# Supercell_1_3.net
KiCad netlist of a schematic drawn in EAGLE
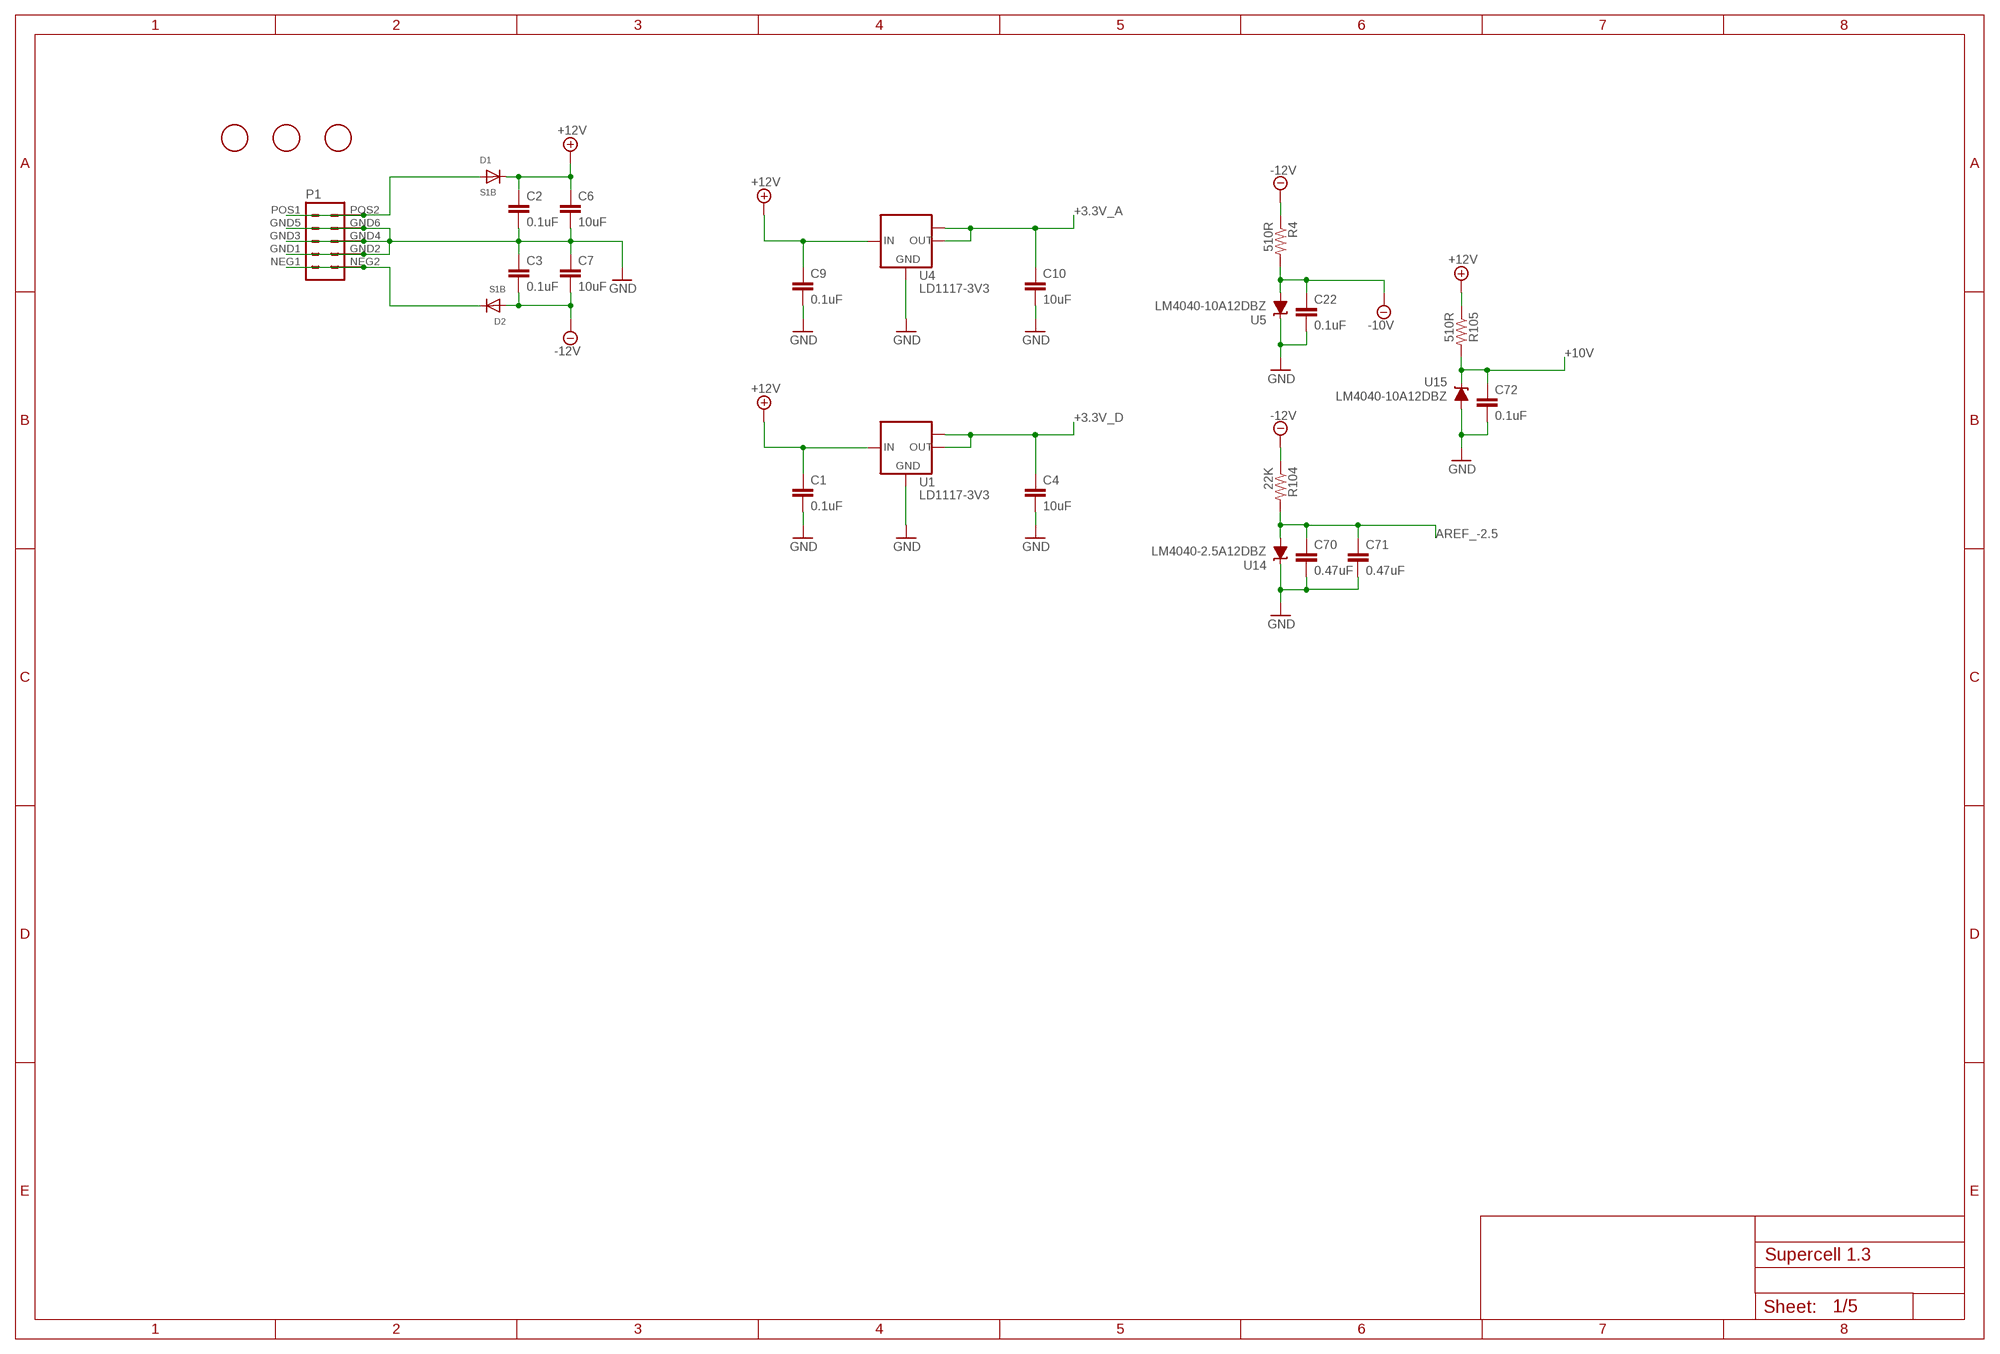
[diagram p0: schematic, sheet 1]
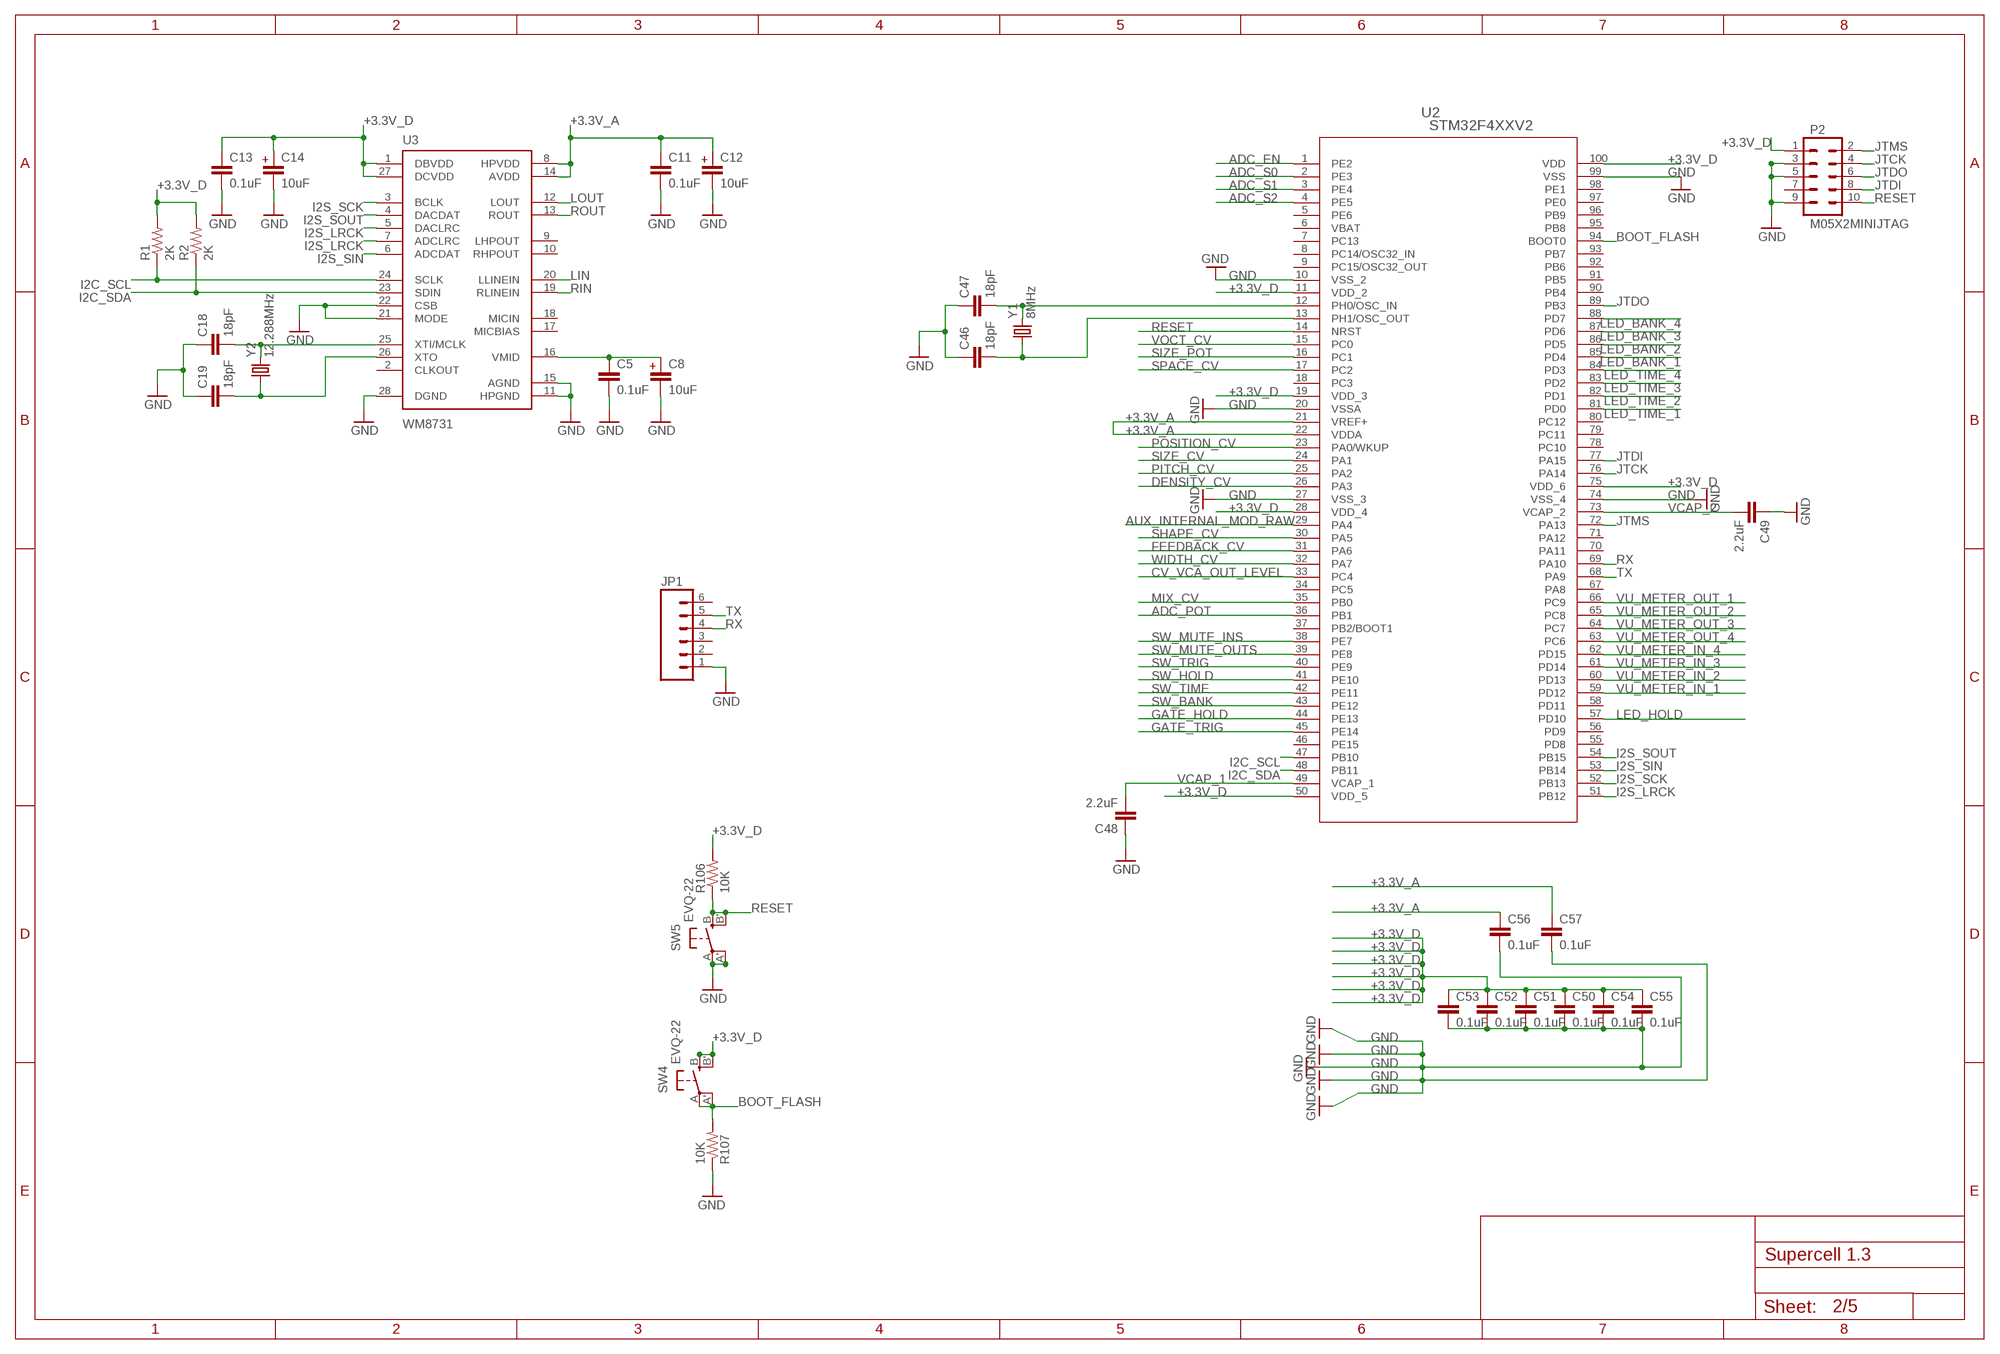
[diagram p1: schematic, sheet 2]
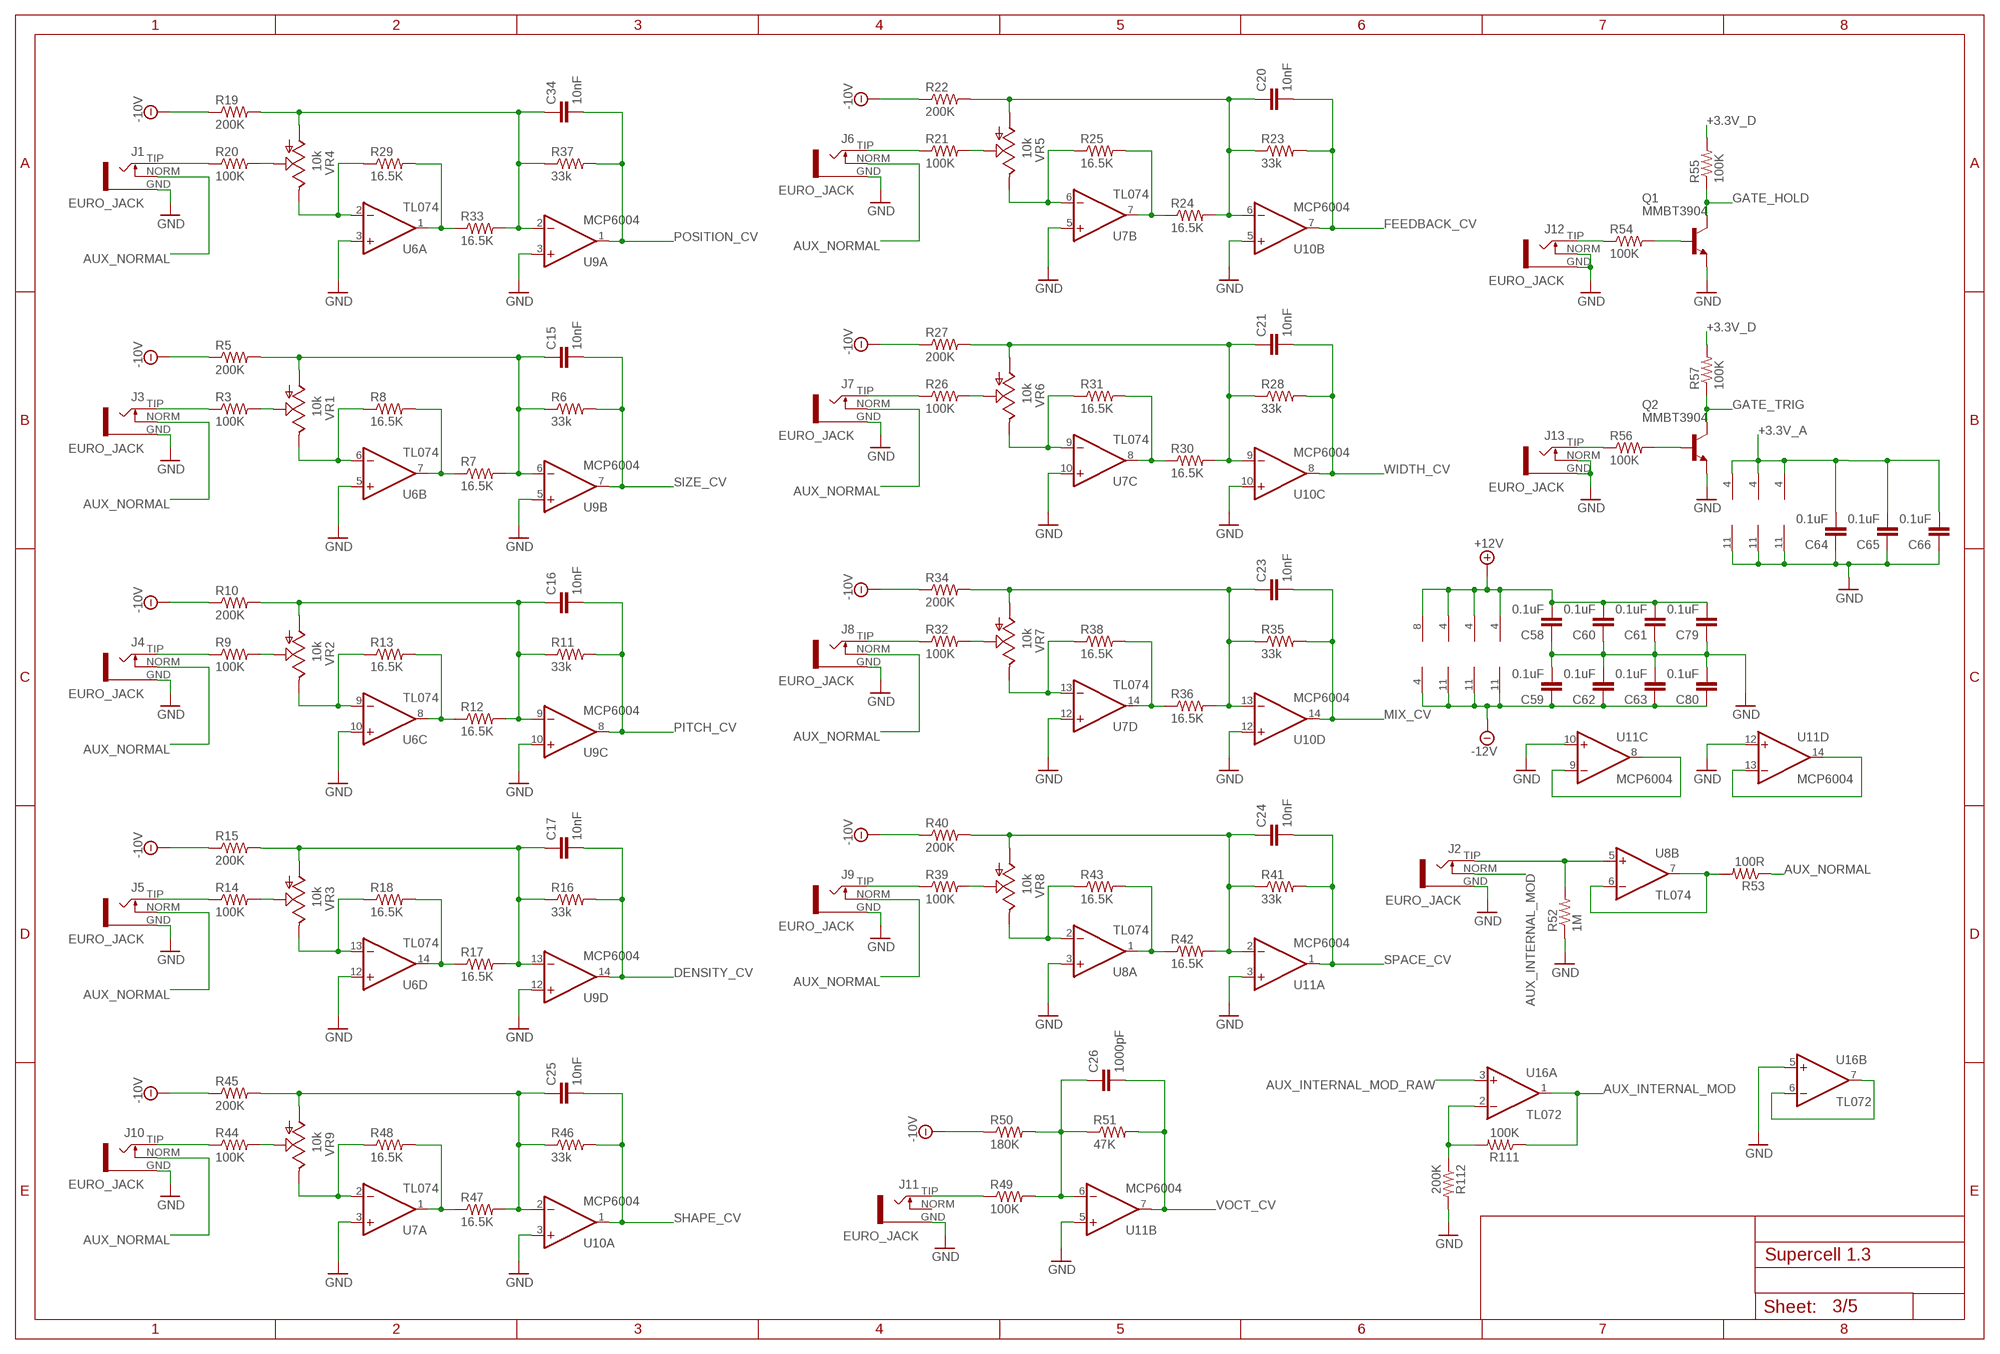
[diagram p2: schematic, sheet 3]
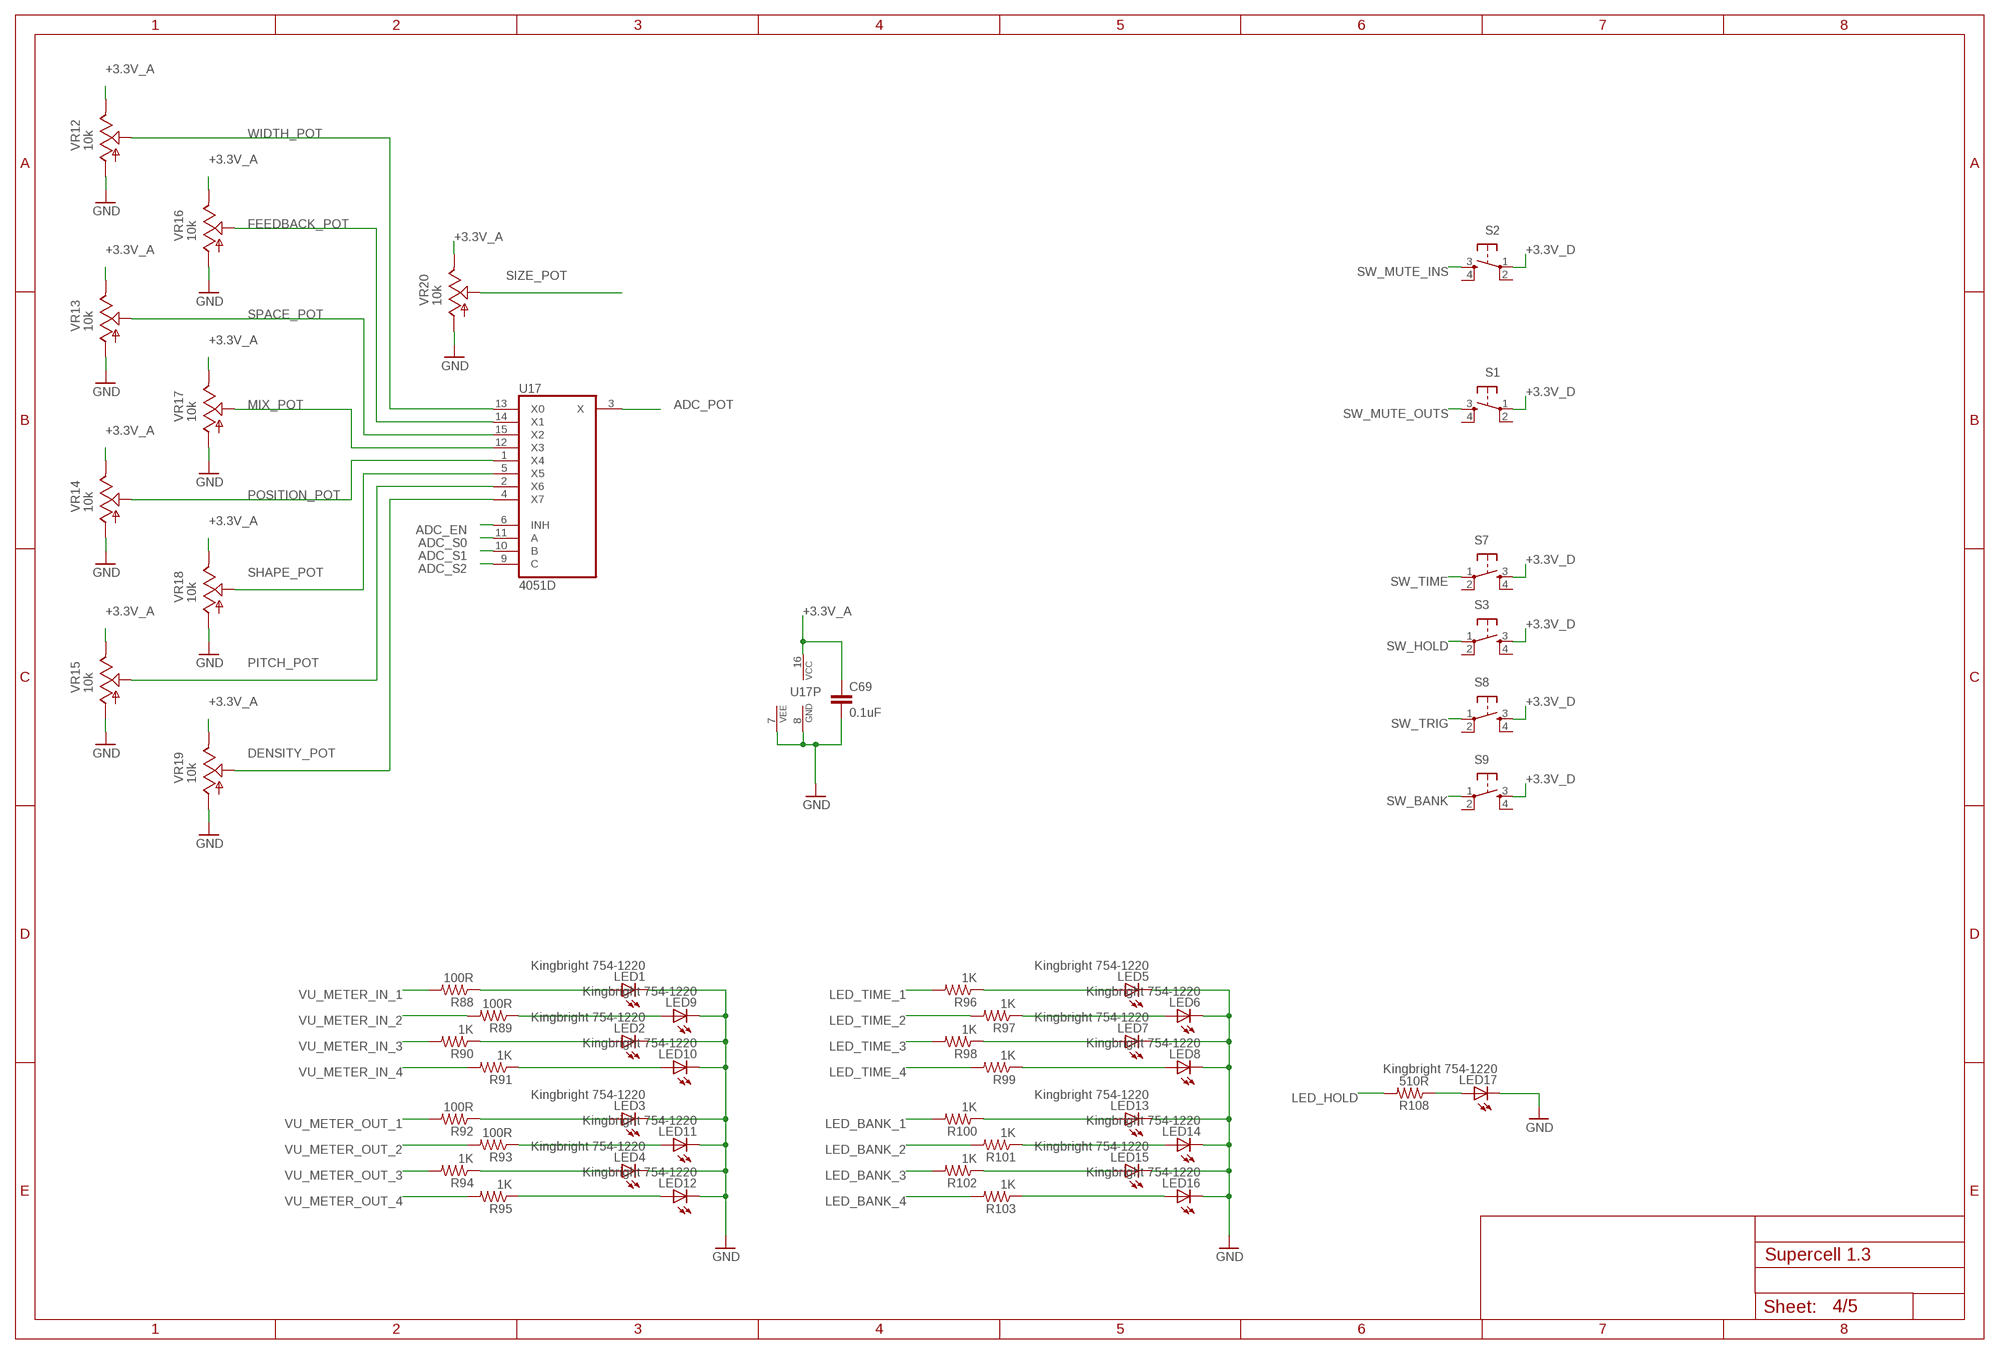
[diagram p3: schematic, sheet 4]
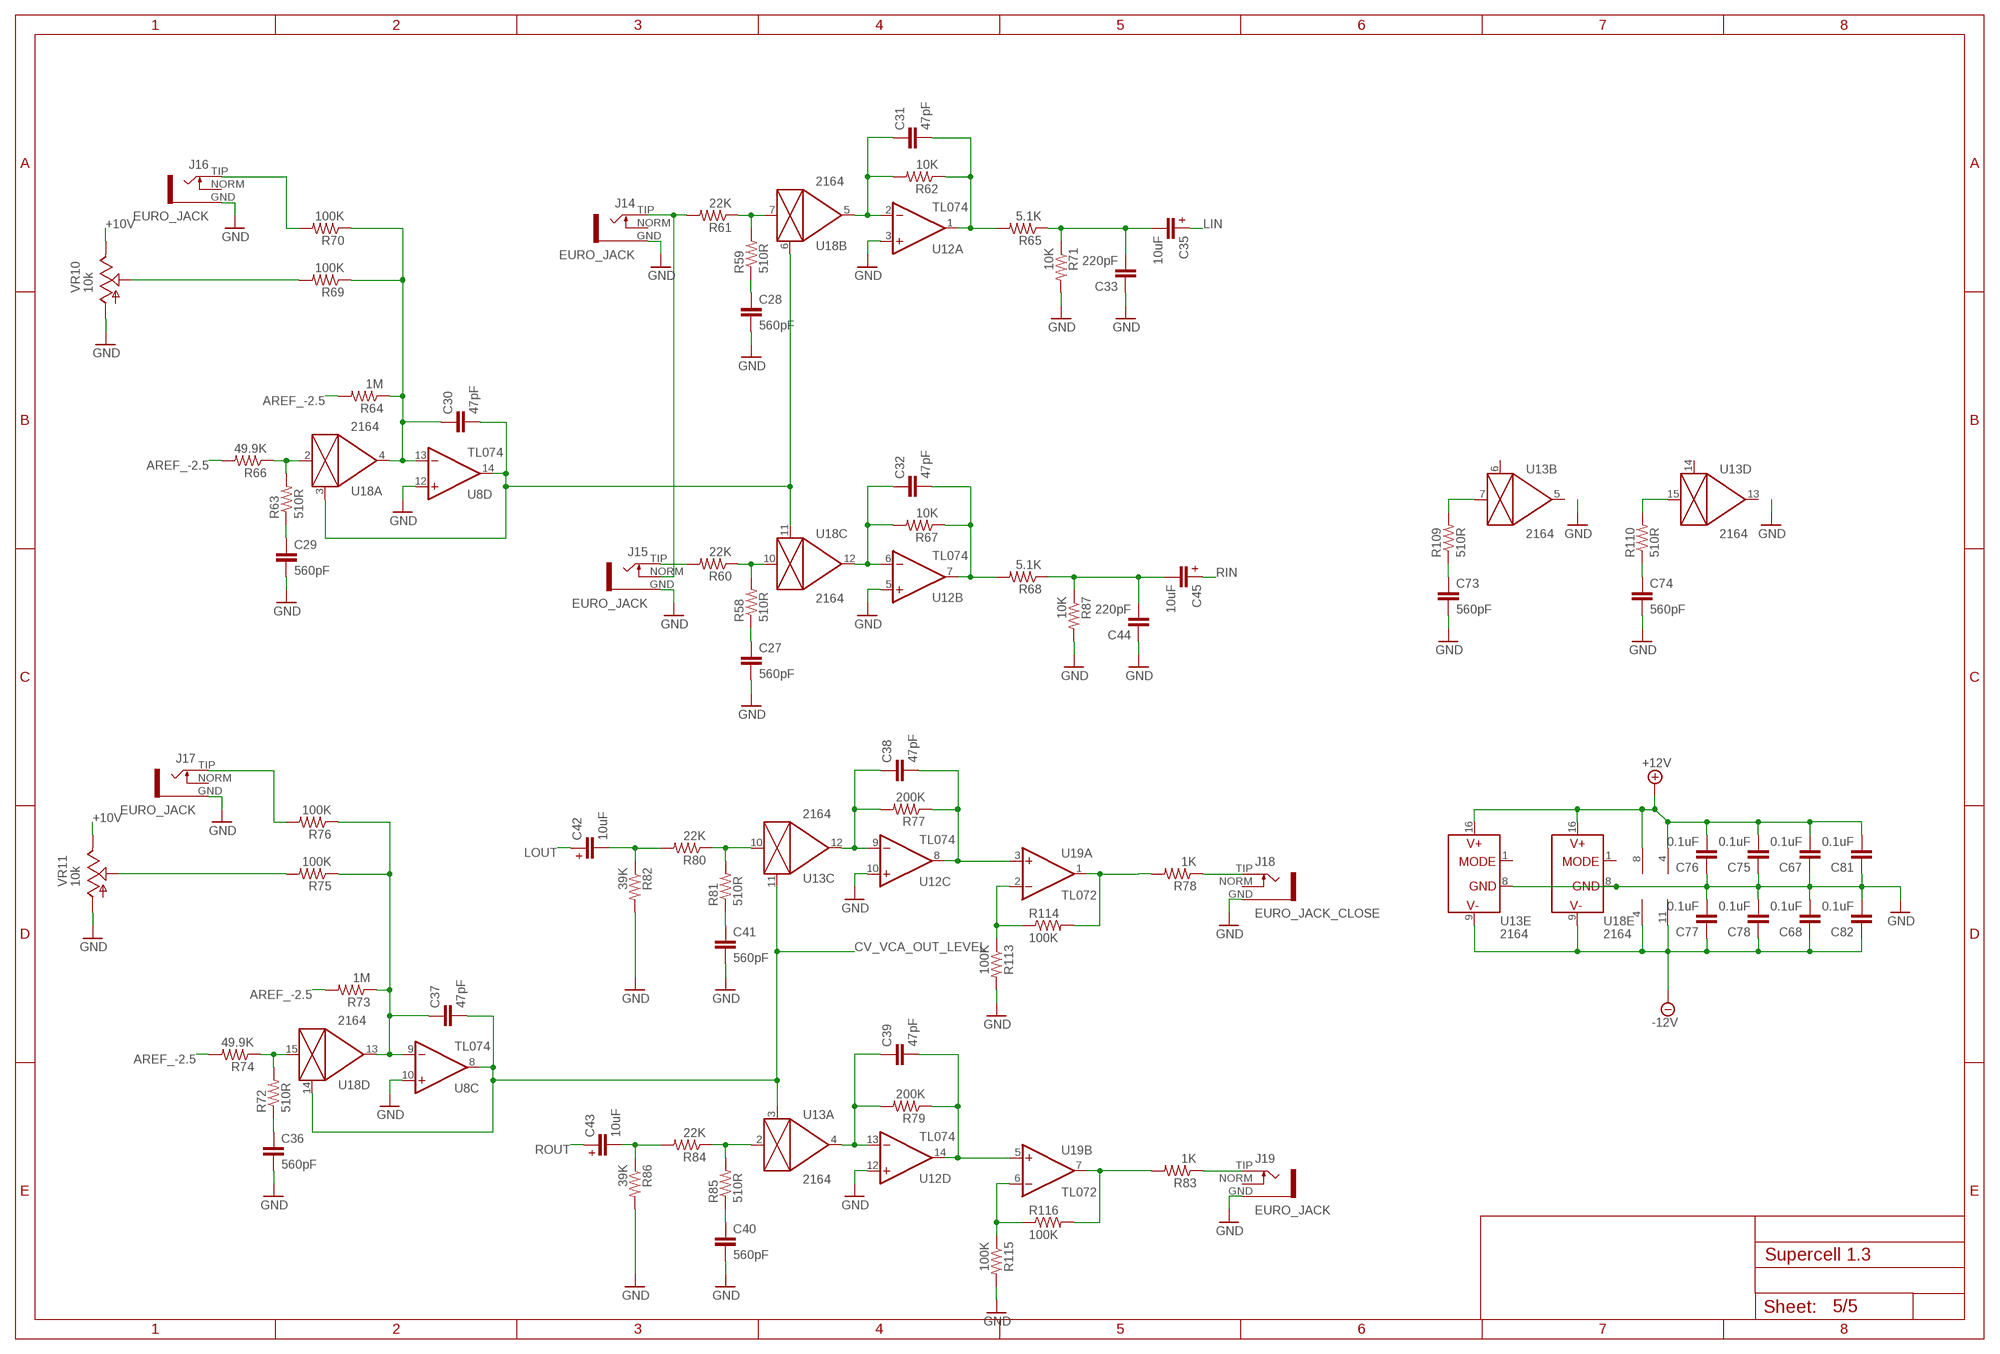
[diagram p4: schematic, sheet 5]

(export (version "E")
  (design (tool "Eeschema 10.0.6"))
  (components
    (comp (ref "C27")
      (value "560pF")
      (footprint "eagle-import:C0603")
      (libsource (lib "eagle-import") (part "rcl_C-EUC0603"))
    )
    (comp (ref "C28")
      (value "560pF")
      (footprint "eagle-import:C0603")
      (libsource (lib "eagle-import") (part "rcl_C-EUC0603"))
    )
    (comp (ref "C29")
      (value "560pF")
      (footprint "eagle-import:C0603")
      (libsource (lib "eagle-import") (part "rcl_C-EUC0603"))
    )
    (comp (ref "C30")
      (value "47pF")
      (footprint "eagle-import:C0603")
      (libsource (lib "eagle-import") (part "rcl_C-EUC0603"))
    )
    (comp (ref "C31")
      (value "47pF")
      (footprint "eagle-import:C0603")
      (libsource (lib "eagle-import") (part "rcl_C-EUC0603"))
    )
    (comp (ref "C32")
      (value "47pF")
      (footprint "eagle-import:C0603")
      (libsource (lib "eagle-import") (part "rcl_C-EUC0603"))
    )
    (comp (ref "C33")
      (value "220pF")
      (footprint "eagle-import:C0603")
      (libsource (lib "eagle-import") (part "rcl_C-EUC0603"))
    )
    (comp (ref "C35")
      (value "10uF")
      (footprint "eagle-import:EC-4X7")
      (libsource (lib "eagle-import") (part "C-EU-POL_4D"))
    )
    (comp (ref "C36")
      (value "560pF")
      (footprint "eagle-import:C0603")
      (libsource (lib "eagle-import") (part "rcl_C-EUC0603"))
    )
    (comp (ref "C37")
      (value "47pF")
      (footprint "eagle-import:C0603")
      (libsource (lib "eagle-import") (part "rcl_C-EUC0603"))
    )
    (comp (ref "C38")
      (value "47pF")
      (footprint "eagle-import:C0603")
      (libsource (lib "eagle-import") (part "rcl_C-EUC0603"))
    )
    (comp (ref "C39")
      (value "47pF")
      (footprint "eagle-import:C0603")
      (libsource (lib "eagle-import") (part "rcl_C-EUC0603"))
    )
    (comp (ref "C40")
      (value "560pF")
      (footprint "eagle-import:C0603")
      (libsource (lib "eagle-import") (part "rcl_C-EUC0603"))
    )
    (comp (ref "C41")
      (value "560pF")
      (footprint "eagle-import:C0603")
      (libsource (lib "eagle-import") (part "rcl_C-EUC0603"))
    )
    (comp (ref "C42")
      (value "10uF")
      (footprint "eagle-import:EC-4X7")
      (libsource (lib "eagle-import") (part "C-EU-POL_4D"))
    )
    (comp (ref "C43")
      (value "10uF")
      (footprint "eagle-import:EC-4X7")
      (libsource (lib "eagle-import") (part "C-EU-POL_4D"))
    )
    (comp (ref "C44")
      (value "220pF")
      (footprint "eagle-import:C0603")
      (libsource (lib "eagle-import") (part "rcl_C-EUC0603"))
    )
    (comp (ref "C45")
      (value "10uF")
      (footprint "eagle-import:EC-4X7")
      (libsource (lib "eagle-import") (part "C-EU-POL_4D"))
    )
    (comp (ref "C67")
      (value "0.1uF")
      (footprint "eagle-import:C0603")
      (libsource (lib "eagle-import") (part "rcl_C-EUC0603"))
    )
    (comp (ref "C68")
      (value "0.1uF")
      (footprint "eagle-import:C0603")
      (libsource (lib "eagle-import") (part "rcl_C-EUC0603"))
    )
    (comp (ref "C73")
      (value "560pF")
      (footprint "eagle-import:C0603")
      (libsource (lib "eagle-import") (part "rcl_C-EUC0603"))
    )
    (comp (ref "C74")
      (value "560pF")
      (footprint "eagle-import:C0603")
      (libsource (lib "eagle-import") (part "rcl_C-EUC0603"))
    )
    (comp (ref "C75")
      (value "0.1uF")
      (footprint "eagle-import:C0603")
      (libsource (lib "eagle-import") (part "rcl_C-EUC0603"))
    )
    (comp (ref "C76")
      (value "0.1uF")
      (footprint "eagle-import:C0603")
      (libsource (lib "eagle-import") (part "rcl_C-EUC0603"))
    )
    (comp (ref "C77")
      (value "0.1uF")
      (footprint "eagle-import:C0603")
      (libsource (lib "eagle-import") (part "rcl_C-EUC0603"))
    )
    (comp (ref "C78")
      (value "0.1uF")
      (footprint "eagle-import:C0603")
      (libsource (lib "eagle-import") (part "rcl_C-EUC0603"))
    )
    (comp (ref "C81")
      (value "0.1uF")
      (footprint "eagle-import:C0603")
      (libsource (lib "eagle-import") (part "rcl_C-EUC0603"))
    )
    (comp (ref "C82")
      (value "0.1uF")
      (footprint "eagle-import:C0603")
      (libsource (lib "eagle-import") (part "rcl_C-EUC0603"))
    )
    (comp (ref "J14")
      (value "EURO_JACK")
      (footprint "eagle-import:S_JACK")
      (libsource (lib "eagle-import") (part "EURO_JACK"))
    )
    (comp (ref "J15")
      (value "EURO_JACK")
      (footprint "eagle-import:S_JACK")
      (libsource (lib "eagle-import") (part "EURO_JACK"))
    )
    (comp (ref "J16")
      (value "EURO_JACK")
      (footprint "eagle-import:S_JACK")
      (libsource (lib "eagle-import") (part "EURO_JACK"))
    )
    (comp (ref "J17")
      (value "EURO_JACK")
      (footprint "eagle-import:S_JACK")
      (libsource (lib "eagle-import") (part "EURO_JACK"))
    )
    (comp (ref "J18")
      (value "EURO_JACK_CLOSE")
      (footprint "eagle-import:S_JACK_CLOSE")
      (libsource (lib "eagle-import") (part "EURO_JACK_CLOSE"))
    )
    (comp (ref "J19")
      (value "EURO_JACK")
      (footprint "eagle-import:S_JACK")
      (libsource (lib "eagle-import") (part "Electrosmith-Interface_EURO_JACK"))
    )
    (comp (ref "R58")
      (value "510R")
      (footprint "eagle-import:R0603")
      (libsource (lib "eagle-import") (part "rcl_R-US_R0603"))
    )
    (comp (ref "R59")
      (value "510R")
      (footprint "eagle-import:R0603")
      (libsource (lib "eagle-import") (part "rcl_R-US_R0603"))
    )
    (comp (ref "R60")
      (value "22K")
      (footprint "eagle-import:R0603")
      (libsource (lib "eagle-import") (part "rcl_R-US_R0603"))
    )
    (comp (ref "R61")
      (value "22K")
      (footprint "eagle-import:R0603")
      (libsource (lib "eagle-import") (part "rcl_R-US_R0603"))
    )
    (comp (ref "R62")
      (value "10K")
      (footprint "eagle-import:R0603")
      (libsource (lib "eagle-import") (part "rcl_R-US_R0603"))
    )
    (comp (ref "R63")
      (value "510R")
      (footprint "eagle-import:R0603")
      (libsource (lib "eagle-import") (part "rcl_R-US_R0603"))
    )
    (comp (ref "R64")
      (value "1M")
      (footprint "eagle-import:R0603")
      (libsource (lib "eagle-import") (part "rcl_R-US_R0603"))
    )
    (comp (ref "R65")
      (value "5.1K")
      (footprint "eagle-import:R0603")
      (libsource (lib "eagle-import") (part "rcl_R-US_R0603"))
    )
    (comp (ref "R66")
      (value "49.9K")
      (footprint "eagle-import:R0603")
      (libsource (lib "eagle-import") (part "rcl_R-US_R0603"))
    )
    (comp (ref "R67")
      (value "10K")
      (footprint "eagle-import:R0603")
      (libsource (lib "eagle-import") (part "rcl_R-US_R0603"))
    )
    (comp (ref "R68")
      (value "5.1K")
      (footprint "eagle-import:R0603")
      (libsource (lib "eagle-import") (part "rcl_R-US_R0603"))
    )
    (comp (ref "R69")
      (value "100K")
      (footprint "eagle-import:R0603")
      (libsource (lib "eagle-import") (part "rcl_R-US_R0603"))
    )
    (comp (ref "R70")
      (value "100K")
      (footprint "eagle-import:R0603")
      (libsource (lib "eagle-import") (part "rcl_R-US_R0603"))
    )
    (comp (ref "R71")
      (value "10K")
      (footprint "eagle-import:R0603")
      (libsource (lib "eagle-import") (part "rcl_R-US_R0603"))
    )
    (comp (ref "R72")
      (value "510R")
      (footprint "eagle-import:R0603")
      (libsource (lib "eagle-import") (part "rcl_R-US_R0603"))
    )
    (comp (ref "R73")
      (value "1M")
      (footprint "eagle-import:R0603")
      (libsource (lib "eagle-import") (part "rcl_R-US_R0603"))
    )
    (comp (ref "R74")
      (value "49.9K")
      (footprint "eagle-import:R0603")
      (libsource (lib "eagle-import") (part "rcl_R-US_R0603"))
    )
    (comp (ref "R75")
      (value "100K")
      (footprint "eagle-import:R0603")
      (libsource (lib "eagle-import") (part "rcl_R-US_R0603"))
    )
    (comp (ref "R76")
      (value "100K")
      (footprint "eagle-import:R0603")
      (libsource (lib "eagle-import") (part "rcl_R-US_R0603"))
    )
    (comp (ref "R77")
      (value "200K")
      (footprint "eagle-import:R0603")
      (libsource (lib "eagle-import") (part "rcl_R-US_R0603"))
    )
    (comp (ref "R78")
      (value "1K")
      (footprint "eagle-import:R0603")
      (libsource (lib "eagle-import") (part "rcl_R-US_R0603"))
    )
    (comp (ref "R79")
      (value "200K")
      (footprint "eagle-import:R0603")
      (libsource (lib "eagle-import") (part "rcl_R-US_R0603"))
    )
    (comp (ref "R80")
      (value "22K")
      (footprint "eagle-import:R0603")
      (libsource (lib "eagle-import") (part "rcl_R-US_R0603"))
    )
    (comp (ref "R81")
      (value "510R")
      (footprint "eagle-import:R0603")
      (libsource (lib "eagle-import") (part "rcl_R-US_R0603"))
    )
    (comp (ref "R82")
      (value "39K")
      (footprint "eagle-import:R0603")
      (libsource (lib "eagle-import") (part "rcl_R-US_R0603"))
    )
    (comp (ref "R83")
      (value "1K")
      (footprint "eagle-import:R0603")
      (libsource (lib "eagle-import") (part "rcl_R-US_R0603"))
    )
    (comp (ref "R84")
      (value "22K")
      (footprint "eagle-import:R0603")
      (libsource (lib "eagle-import") (part "rcl_R-US_R0603"))
    )
    (comp (ref "R85")
      (value "510R")
      (footprint "eagle-import:R0603")
      (libsource (lib "eagle-import") (part "rcl_R-US_R0603"))
    )
    (comp (ref "R86")
      (value "39K")
      (footprint "eagle-import:R0603")
      (libsource (lib "eagle-import") (part "rcl_R-US_R0603"))
    )
    (comp (ref "R87")
      (value "10K")
      (footprint "eagle-import:R0603")
      (libsource (lib "eagle-import") (part "rcl_R-US_R0603"))
    )
    (comp (ref "R109")
      (value "510R")
      (footprint "eagle-import:R0603")
      (libsource (lib "eagle-import") (part "rcl_R-US_R0603"))
    )
    (comp (ref "R110")
      (value "510R")
      (footprint "eagle-import:R0603")
      (libsource (lib "eagle-import") (part "rcl_R-US_R0603"))
    )
    (comp (ref "R113")
      (value "100K")
      (footprint "eagle-import:R0603")
      (libsource (lib "eagle-import") (part "rcl_R-US_R0603"))
    )
    (comp (ref "R114")
      (value "100K")
      (footprint "eagle-import:R0603")
      (libsource (lib "eagle-import") (part "rcl_R-US_R0603"))
    )
    (comp (ref "R115")
      (value "100K")
      (footprint "eagle-import:R0603")
      (libsource (lib "eagle-import") (part "rcl_R-US_R0603"))
    )
    (comp (ref "R116")
      (value "100K")
      (footprint "eagle-import:R0603")
      (libsource (lib "eagle-import") (part "rcl_R-US_R0603"))
    )
    (comp (ref "U8")
      (value "TL074")
      (footprint "eagle-import:SO14")
      (libsource (lib "eagle-import") (part "QUAD_OPAMPD"))
    )
    (comp (ref "U12")
      (value "TL074")
      (footprint "eagle-import:SO14")
      (libsource (lib "eagle-import") (part "QUAD_OPAMPD"))
    )
    (comp (ref "U13")
      (value "2164")
      (footprint "eagle-import:SO16")
      (libsource (lib "eagle-import") (part "SSM2164S"))
    )
    (comp (ref "U18")
      (value "2164")
      (footprint "eagle-import:SO16")
      (libsource (lib "eagle-import") (part "SSM2164S"))
    )
    (comp (ref "U19")
      (value "TL072")
      (footprint "eagle-import:SO08_BOXPIN")
      (libsource (lib "eagle-import") (part "DUAL_OPAMP"))
    )
    (comp (ref "VR10")
      (value "10k")
      (footprint "eagle-import:9MM_SNAP-IN_POT_NO_SILK")
      (libsource (lib "eagle-import") (part "POT_9MM_SNAP-IN_"))
    )
    (comp (ref "VR11")
      (value "10k")
      (footprint "eagle-import:9MM_SNAP-IN_POT_NO_SILK")
      (libsource (lib "eagle-import") (part "POT_9MM_SNAP-IN_"))
    )
    (comp (ref "C1")
      (value "0.1uF")
      (footprint "eagle-import:C0603")
      (libsource (lib "eagle-import") (part "rcl_C-EUC0603"))
    )
    (comp (ref "C2")
      (value "0.1uF")
      (footprint "eagle-import:C0603")
      (libsource (lib "eagle-import") (part "rcl_C-EUC0603"))
    )
    (comp (ref "C3")
      (value "0.1uF")
      (footprint "eagle-import:C0603")
      (libsource (lib "eagle-import") (part "rcl_C-EUC0603"))
    )
    (comp (ref "C4")
      (value "10uF")
      (footprint "eagle-import:C0805")
      (libsource (lib "eagle-import") (part "C-EUC0805"))
    )
    (comp (ref "C6")
      (value "10uF")
      (footprint "eagle-import:C0805")
      (libsource (lib "eagle-import") (part "C-EUC0805"))
    )
    (comp (ref "C7")
      (value "10uF")
      (footprint "eagle-import:C0805")
      (libsource (lib "eagle-import") (part "C-EUC0805"))
    )
    (comp (ref "C9")
      (value "0.1uF")
      (footprint "eagle-import:C0603")
      (libsource (lib "eagle-import") (part "rcl_C-EUC0603"))
    )
    (comp (ref "C10")
      (value "10uF")
      (footprint "eagle-import:C0805")
      (libsource (lib "eagle-import") (part "C-EUC0805"))
    )
    (comp (ref "C22")
      (value "0.1uF")
      (footprint "eagle-import:C0603")
      (libsource (lib "eagle-import") (part "C-EUC0603"))
    )
    (comp (ref "C70")
      (value "0.47uF")
      (footprint "eagle-import:C0603")
      (libsource (lib "eagle-import") (part "C-EUC0603"))
    )
    (comp (ref "C71")
      (value "0.47uF")
      (footprint "eagle-import:C0603")
      (libsource (lib "eagle-import") (part "C-EUC0603"))
    )
    (comp (ref "C72")
      (value "0.1uF")
      (footprint "eagle-import:C0603")
      (libsource (lib "eagle-import") (part "C-EUC0603"))
    )
    (comp (ref "D1")
      (value "S1B")
      (footprint "eagle-import:SMADIODE")
      (libsource (lib "eagle-import") (part "DIODESMA"))
    )
    (comp (ref "D2")
      (value "S1B")
      (footprint "eagle-import:SMADIODE")
      (libsource (lib "eagle-import") (part "DIODESMA"))
    )
    (comp (ref "FD1")
      (value "FIDUCIAL")
      (footprint "eagle-import:FIDUCIAL_1MM")
      (libsource (lib "eagle-import") (part "FIDUCIAL"))
    )
    (comp (ref "FD2")
      (value "FIDUCIAL")
      (footprint "eagle-import:FIDUCIAL_1MM")
      (libsource (lib "eagle-import") (part "FIDUCIAL"))
    )
    (comp (ref "FD3")
      (value "FIDUCIAL")
      (footprint "eagle-import:FIDUCIAL_1MM")
      (libsource (lib "eagle-import") (part "FIDUCIAL"))
    )
    (comp (ref "P1")
      (value "EURO_POWER_HEADERLOCK_PADS")
      (footprint "eagle-import:EURO_PWR_HEADER_LOCK")
      (libsource (lib "eagle-import") (part "EURO_POWER_HEADERLOCK_PADS"))
    )
    (comp (ref "R4")
      (value "510R")
      (footprint "eagle-import:R0603")
      (libsource (lib "eagle-import") (part "rcl_R-US_R0603"))
    )
    (comp (ref "R104")
      (value "22K")
      (footprint "eagle-import:R0603")
      (libsource (lib "eagle-import") (part "rcl_R-US_R0603"))
    )
    (comp (ref "R105")
      (value "510R")
      (footprint "eagle-import:R0603")
      (libsource (lib "eagle-import") (part "rcl_R-US_R0603"))
    )
    (comp (ref "U1")
      (value "LD1117-3V3")
      (footprint "eagle-import:SOT223")
      (libsource (lib "eagle-import") (part "LM1117MPX-3.3"))
    )
    (comp (ref "U4")
      (value "LD1117-3V3")
      (footprint "eagle-import:SOT223")
      (libsource (lib "eagle-import") (part "LM1117MPX-3.3"))
    )
    (comp (ref "U5")
      (value "LM4040-10A12DBZ")
      (footprint "eagle-import:DBZ_R-PDSO-G3")
      (fields (field (name "MPN") "LM4041A12IDBZR"))
      (libsource (lib "eagle-import") (part "LM4040-10DBZA12"))
    )
    (comp (ref "U14")
      (value "LM4040-2.5A12DBZ")
      (footprint "eagle-import:DBZ_R-PDSO-G3")
      (fields (field (name "MPN") "LM4041A12IDBZR"))
      (libsource (lib "eagle-import") (part "LM4040-2.5DBZA12"))
    )
    (comp (ref "U15")
      (value "LM4040-10A12DBZ")
      (footprint "eagle-import:DBZ_R-PDSO-G3")
      (fields (field (name "MPN") "LM4041A12IDBZR"))
      (libsource (lib "eagle-import") (part "LM4040-10DBZA12"))
    )
    (comp (ref "C5")
      (value "0.1uF")
      (footprint "eagle-import:C0603")
      (libsource (lib "eagle-import") (part "ElectroSmith_C-EUC0603"))
    )
    (comp (ref "C8")
      (value "10uF")
      (footprint "eagle-import:EC-4X7")
      (libsource (lib "eagle-import") (part "C-EU-POL_4D"))
    )
    (comp (ref "C11")
      (value "0.1uF")
      (footprint "eagle-import:C0603")
      (libsource (lib "eagle-import") (part "ElectroSmith_C-EUC0603"))
    )
    (comp (ref "C12")
      (value "10uF")
      (footprint "eagle-import:EC-4X7")
      (libsource (lib "eagle-import") (part "C-EU-POL_4D"))
    )
    (comp (ref "C13")
      (value "0.1uF")
      (footprint "eagle-import:C0603")
      (libsource (lib "eagle-import") (part "ElectroSmith_C-EUC0603"))
    )
    (comp (ref "C14")
      (value "10uF")
      (footprint "eagle-import:EC-4X7")
      (libsource (lib "eagle-import") (part "C-EU-POL_4D"))
    )
    (comp (ref "C18")
      (value "18pF")
      (footprint "eagle-import:C0603")
      (libsource (lib "eagle-import") (part "ElectroSmith_C-EUC0603"))
    )
    (comp (ref "C19")
      (value "18pF")
      (footprint "eagle-import:C0603")
      (libsource (lib "eagle-import") (part "ElectroSmith_C-EUC0603"))
    )
    (comp (ref "C46")
      (value "18pF")
      (footprint "eagle-import:C0603")
      (libsource (lib "eagle-import") (part "ElectroSmith_C-EUC0603"))
    )
    (comp (ref "C47")
      (value "18pF")
      (footprint "eagle-import:C0603")
      (libsource (lib "eagle-import") (part "ElectroSmith_C-EUC0603"))
    )
    (comp (ref "C48")
      (value "2.2uF")
      (footprint "eagle-import:C0603")
      (libsource (lib "eagle-import") (part "ElectroSmith_C-EUC0603"))
    )
    (comp (ref "C49")
      (value "2.2uF")
      (footprint "eagle-import:C0603")
      (libsource (lib "eagle-import") (part "ElectroSmith_C-EUC0603"))
    )
    (comp (ref "C50")
      (value "0.1uF")
      (footprint "eagle-import:C0603")
      (libsource (lib "eagle-import") (part "ElectroSmith_C-EUC0603"))
    )
    (comp (ref "C51")
      (value "0.1uF")
      (footprint "eagle-import:C0603")
      (libsource (lib "eagle-import") (part "ElectroSmith_C-EUC0603"))
    )
    (comp (ref "C52")
      (value "0.1uF")
      (footprint "eagle-import:C0603")
      (libsource (lib "eagle-import") (part "ElectroSmith_C-EUC0603"))
    )
    (comp (ref "C53")
      (value "0.1uF")
      (footprint "eagle-import:C0603")
      (libsource (lib "eagle-import") (part "ElectroSmith_C-EUC0603"))
    )
    (comp (ref "C54")
      (value "0.1uF")
      (footprint "eagle-import:C0603")
      (libsource (lib "eagle-import") (part "ElectroSmith_C-EUC0603"))
    )
    (comp (ref "C55")
      (value "0.1uF")
      (footprint "eagle-import:C0603")
      (libsource (lib "eagle-import") (part "ElectroSmith_C-EUC0603"))
    )
    (comp (ref "C56")
      (value "0.1uF")
      (footprint "eagle-import:C0603")
      (libsource (lib "eagle-import") (part "ElectroSmith_C-EUC0603"))
    )
    (comp (ref "C57")
      (value "0.1uF")
      (footprint "eagle-import:C0603")
      (libsource (lib "eagle-import") (part "ElectroSmith_C-EUC0603"))
    )
    (comp (ref "JP1")
      (value "M06SIP")
      (footprint "eagle-import:1X06")
      (libsource (lib "eagle-import") (part "M06SIP"))
    )
    (comp (ref "P2")
      (value "M05X2MINIJTAG")
      (footprint "eagle-import:2X5-1.27")
      (libsource (lib "eagle-import") (part "M05X2MINIJTAG"))
    )
    (comp (ref "R1")
      (value "2K")
      (footprint "eagle-import:R0603")
      (libsource (lib "eagle-import") (part "resistor_348_R-US_R0603"))
    )
    (comp (ref "R2")
      (value "2K")
      (footprint "eagle-import:R0603")
      (libsource (lib "eagle-import") (part "resistor_348_R-US_R0603"))
    )
    (comp (ref "R106")
      (value "10K")
      (footprint "eagle-import:R0603")
      (libsource (lib "eagle-import") (part "rcl_R-US_R0603"))
    )
    (comp (ref "R107")
      (value "10K")
      (footprint "eagle-import:R0603")
      (libsource (lib "eagle-import") (part "rcl_R-US_R0603"))
    )
    (comp (ref "SW4")
      (value "EVQ-22")
      (footprint "eagle-import:EVQ-Q2")
      (libsource (lib "eagle-import") (part "EVQQ2"))
    )
    (comp (ref "SW5")
      (value "EVQ-22")
      (footprint "eagle-import:EVQ-Q2")
      (libsource (lib "eagle-import") (part "EVQQ2"))
    )
    (comp (ref "U2")
      (value "STM32F4XXV2")
      (footprint "eagle-import:LQFP100-14X14MM")
      (fields (field (name "MANUFACTURER_PART_NUMBER") "stm32f4xxv2"))
      (libsource (lib "eagle-import") (part "STM32F4XXV2"))
    )
    (comp (ref "U3")
      (value "WM8731")
      (footprint "eagle-import:SSOP28")
      (libsource (lib "eagle-import") (part "WM8731"))
    )
    (comp (ref "Y1")
      (value "8MHz")
      (footprint "eagle-import:HC49UP")
      (libsource (lib "eagle-import") (part "CRYSTALHC49UP"))
    )
    (comp (ref "Y2")
      (value "12.288MHz")
      (footprint "eagle-import:HC49UP")
      (libsource (lib "eagle-import") (part "CRYSTALHC49UP"))
    )
    (comp (ref "C69")
      (value "0.1uF")
      (footprint "eagle-import:C0603")
      (libsource (lib "eagle-import") (part "ElectroSmith_C-EUC0603"))
    )
    (comp (ref "LED1")
      (value "Kingbright 754-1220")
      (footprint "eagle-import:LED_3MM_MIN")
      (libsource (lib "eagle-import") (part "LED_3MM_MIN"))
    )
    (comp (ref "LED2")
      (value "Kingbright 754-1220")
      (footprint "eagle-import:LED_3MM_MIN")
      (libsource (lib "eagle-import") (part "LED_3MM_MIN"))
    )
    (comp (ref "LED3")
      (value "Kingbright 754-1220")
      (footprint "eagle-import:LED_3MM_MIN")
      (libsource (lib "eagle-import") (part "LED_3MM_MIN"))
    )
    (comp (ref "LED4")
      (value "Kingbright 754-1220")
      (footprint "eagle-import:LED_3MM_MIN")
      (libsource (lib "eagle-import") (part "LED_3MM_MIN"))
    )
    (comp (ref "LED5")
      (value "Kingbright 754-1220")
      (footprint "eagle-import:LED_3MM_MIN")
      (libsource (lib "eagle-import") (part "LED_3MM_MIN"))
    )
    (comp (ref "LED6")
      (value "Kingbright 754-1220")
      (footprint "eagle-import:LED_3MM_MIN")
      (libsource (lib "eagle-import") (part "LED_3MM_MIN"))
    )
    (comp (ref "LED7")
      (value "Kingbright 754-1220")
      (footprint "eagle-import:LED_3MM_MIN")
      (libsource (lib "eagle-import") (part "LED_3MM_MIN"))
    )
    (comp (ref "LED8")
      (value "Kingbright 754-1220")
      (footprint "eagle-import:LED_3MM_MIN")
      (libsource (lib "eagle-import") (part "LED_3MM_MIN"))
    )
    (comp (ref "LED9")
      (value "Kingbright 754-1220")
      (footprint "eagle-import:LED_3MM_MIN")
      (libsource (lib "eagle-import") (part "LED_3MM_MIN"))
    )
    (comp (ref "LED10")
      (value "Kingbright 754-1220")
      (footprint "eagle-import:LED_3MM_MIN")
      (libsource (lib "eagle-import") (part "LED_3MM_MIN"))
    )
    (comp (ref "LED11")
      (value "Kingbright 754-1220")
      (footprint "eagle-import:LED_3MM_MIN")
      (libsource (lib "eagle-import") (part "LED_3MM_MIN"))
    )
    (comp (ref "LED12")
      (value "Kingbright 754-1220")
      (footprint "eagle-import:LED_3MM_MIN")
      (libsource (lib "eagle-import") (part "LED_3MM_MIN"))
    )
    (comp (ref "LED13")
      (value "Kingbright 754-1220")
      (footprint "eagle-import:LED_3MM_MIN")
      (libsource (lib "eagle-import") (part "LED_3MM_MIN"))
    )
    (comp (ref "LED14")
      (value "Kingbright 754-1220")
      (footprint "eagle-import:LED_3MM_MIN")
      (libsource (lib "eagle-import") (part "LED_3MM_MIN"))
    )
    (comp (ref "LED15")
      (value "Kingbright 754-1220")
      (footprint "eagle-import:LED_3MM_MIN")
      (libsource (lib "eagle-import") (part "LED_3MM_MIN"))
    )
    (comp (ref "LED16")
      (value "Kingbright 754-1220")
      (footprint "eagle-import:LED_3MM_MIN")
      (libsource (lib "eagle-import") (part "LED_3MM_MIN"))
    )
    (comp (ref "LED17")
      (value "Kingbright 754-1220")
      (footprint "eagle-import:LED_3MM_MIN")
      (libsource (lib "eagle-import") (part "LED_3MM_MIN"))
    )
    (comp (ref "R88")
      (value "100R")
      (footprint "eagle-import:R0603")
      (libsource (lib "eagle-import") (part "R-US_R0603"))
    )
    (comp (ref "R89")
      (value "100R")
      (footprint "eagle-import:R0603")
      (libsource (lib "eagle-import") (part "R-US_R0603"))
    )
    (comp (ref "R90")
      (value "1K")
      (footprint "eagle-import:R0603")
      (libsource (lib "eagle-import") (part "R-US_R0603"))
    )
    (comp (ref "R91")
      (value "1K")
      (footprint "eagle-import:R0603")
      (libsource (lib "eagle-import") (part "R-US_R0603"))
    )
    (comp (ref "R92")
      (value "100R")
      (footprint "eagle-import:R0603")
      (libsource (lib "eagle-import") (part "R-US_R0603"))
    )
    (comp (ref "R93")
      (value "100R")
      (footprint "eagle-import:R0603")
      (libsource (lib "eagle-import") (part "R-US_R0603"))
    )
    (comp (ref "R94")
      (value "1K")
      (footprint "eagle-import:R0603")
      (libsource (lib "eagle-import") (part "R-US_R0603"))
    )
    (comp (ref "R95")
      (value "1K")
      (footprint "eagle-import:R0603")
      (libsource (lib "eagle-import") (part "R-US_R0603"))
    )
    (comp (ref "R96")
      (value "1K")
      (footprint "eagle-import:R0603")
      (libsource (lib "eagle-import") (part "R-US_R0603"))
    )
    (comp (ref "R97")
      (value "1K")
      (footprint "eagle-import:R0603")
      (libsource (lib "eagle-import") (part "R-US_R0603"))
    )
    (comp (ref "R98")
      (value "1K")
      (footprint "eagle-import:R0603")
      (libsource (lib "eagle-import") (part "R-US_R0603"))
    )
    (comp (ref "R99")
      (value "1K")
      (footprint "eagle-import:R0603")
      (libsource (lib "eagle-import") (part "R-US_R0603"))
    )
    (comp (ref "R100")
      (value "1K")
      (footprint "eagle-import:R0603")
      (libsource (lib "eagle-import") (part "R-US_R0603"))
    )
    (comp (ref "R101")
      (value "1K")
      (footprint "eagle-import:R0603")
      (libsource (lib "eagle-import") (part "R-US_R0603"))
    )
    (comp (ref "R102")
      (value "1K")
      (footprint "eagle-import:R0603")
      (libsource (lib "eagle-import") (part "R-US_R0603"))
    )
    (comp (ref "R103")
      (value "1K")
      (footprint "eagle-import:R0603")
      (libsource (lib "eagle-import") (part "R-US_R0603"))
    )
    (comp (ref "R108")
      (value "510R")
      (footprint "eagle-import:R0603")
      (libsource (lib "eagle-import") (part "R-US_R0603"))
    )
    (comp (ref "S1")
      (value "TAC_SWITCHPTH")
      (footprint "eagle-import:TACTILE-PTH")
      (libsource (lib "eagle-import") (part "TAC_SWITCHPTH"))
    )
    (comp (ref "S2")
      (value "TAC_SWITCHPTH")
      (footprint "eagle-import:TACTILE-PTH")
      (libsource (lib "eagle-import") (part "TAC_SWITCHPTH"))
    )
    (comp (ref "S3")
      (value "TAC_SWITCH")
      (footprint "eagle-import:C&K_D6R")
      (libsource (lib "eagle-import") (part "TAC_SWITCH"))
    )
    (comp (ref "S7")
      (value "TAC_SWITCH")
      (footprint "eagle-import:C&K_D6R")
      (libsource (lib "eagle-import") (part "TAC_SWITCH"))
    )
    (comp (ref "S8")
      (value "TAC_SWITCH")
      (footprint "eagle-import:C&K_D6R")
      (libsource (lib "eagle-import") (part "TAC_SWITCH"))
    )
    (comp (ref "S9")
      (value "TAC_SWITCH")
      (footprint "eagle-import:C&K_D6R")
      (libsource (lib "eagle-import") (part "TAC_SWITCH"))
    )
    (comp (ref "U17")
      (value "4051D")
      (footprint "eagle-import:SO16")
      (libsource (lib "eagle-import") (part "4051D"))
    )
    (comp (ref "VR12")
      (value "10k")
      (footprint "eagle-import:9MM_SNAP-IN_POT_NO_SILK")
      (libsource (lib "eagle-import") (part "POT_9MM_SNAP-IN_"))
    )
    (comp (ref "VR13")
      (value "10k")
      (footprint "eagle-import:9MM_SNAP-IN_POT_NO_SILK")
      (libsource (lib "eagle-import") (part "POT_9MM_SNAP-IN_"))
    )
    (comp (ref "VR14")
      (value "10k")
      (footprint "eagle-import:9MM_SNAP-IN_POT_NO_SILK")
      (libsource (lib "eagle-import") (part "POT_9MM_SNAP-IN_"))
    )
    (comp (ref "VR15")
      (value "10k")
      (footprint "eagle-import:9MM_SNAP-IN_POT_NO_SILK")
      (libsource (lib "eagle-import") (part "POT_9MM_SNAP-IN_"))
    )
    (comp (ref "VR16")
      (value "10k")
      (footprint "eagle-import:9MM_SNAP-IN_POT_NO_SILK")
      (libsource (lib "eagle-import") (part "POT_9MM_SNAP-IN_"))
    )
    (comp (ref "VR17")
      (value "10k")
      (footprint "eagle-import:9MM_SNAP-IN_POT_NO_SILK")
      (libsource (lib "eagle-import") (part "POT_9MM_SNAP-IN_"))
    )
    (comp (ref "VR18")
      (value "10k")
      (footprint "eagle-import:9MM_SNAP-IN_POT_NO_SILK")
      (libsource (lib "eagle-import") (part "POT_9MM_SNAP-IN_"))
    )
    (comp (ref "VR19")
      (value "10k")
      (footprint "eagle-import:9MM_SNAP-IN_POT_NO_SILK")
      (libsource (lib "eagle-import") (part "POT_9MM_SNAP-IN_"))
    )
    (comp (ref "VR20")
      (value "10k")
      (footprint "eagle-import:9MM_SNAP-IN_POT_NO_SILK")
      (libsource (lib "eagle-import") (part "POT_9MM_SNAP-IN_"))
    )
    (comp (ref "C15")
      (value "10nF")
      (footprint "eagle-import:C0603")
      (libsource (lib "eagle-import") (part "ElectroSmith_C-EUC0603"))
    )
    (comp (ref "C16")
      (value "10nF")
      (footprint "eagle-import:C0603")
      (libsource (lib "eagle-import") (part "ElectroSmith_C-EUC0603"))
    )
    (comp (ref "C17")
      (value "10nF")
      (footprint "eagle-import:C0603")
      (libsource (lib "eagle-import") (part "ElectroSmith_C-EUC0603"))
    )
    (comp (ref "C20")
      (value "10nF")
      (footprint "eagle-import:C0603")
      (libsource (lib "eagle-import") (part "ElectroSmith_C-EUC0603"))
    )
    (comp (ref "C21")
      (value "10nF")
      (footprint "eagle-import:C0603")
      (libsource (lib "eagle-import") (part "ElectroSmith_C-EUC0603"))
    )
    (comp (ref "C23")
      (value "10nF")
      (footprint "eagle-import:C0603")
      (libsource (lib "eagle-import") (part "ElectroSmith_C-EUC0603"))
    )
    (comp (ref "C24")
      (value "10nF")
      (footprint "eagle-import:C0603")
      (libsource (lib "eagle-import") (part "ElectroSmith_C-EUC0603"))
    )
    (comp (ref "C25")
      (value "10nF")
      (footprint "eagle-import:C0603")
      (libsource (lib "eagle-import") (part "ElectroSmith_C-EUC0603"))
    )
    (comp (ref "C26")
      (value "1000pF")
      (footprint "eagle-import:C0603")
      (libsource (lib "eagle-import") (part "ElectroSmith_C-EUC0603"))
    )
    (comp (ref "C34")
      (value "10nF")
      (footprint "eagle-import:C0603")
      (libsource (lib "eagle-import") (part "ElectroSmith_C-EUC0603"))
    )
    (comp (ref "C58")
      (value "0.1uF")
      (footprint "eagle-import:C0603")
      (libsource (lib "eagle-import") (part "ElectroSmith_C-EUC0603"))
    )
    (comp (ref "C59")
      (value "0.1uF")
      (footprint "eagle-import:C0603")
      (libsource (lib "eagle-import") (part "ElectroSmith_C-EUC0603"))
    )
    (comp (ref "C60")
      (value "0.1uF")
      (footprint "eagle-import:C0603")
      (libsource (lib "eagle-import") (part "ElectroSmith_C-EUC0603"))
    )
    (comp (ref "C61")
      (value "0.1uF")
      (footprint "eagle-import:C0603")
      (libsource (lib "eagle-import") (part "ElectroSmith_C-EUC0603"))
    )
    (comp (ref "C62")
      (value "0.1uF")
      (footprint "eagle-import:C0603")
      (libsource (lib "eagle-import") (part "ElectroSmith_C-EUC0603"))
    )
    (comp (ref "C63")
      (value "0.1uF")
      (footprint "eagle-import:C0603")
      (libsource (lib "eagle-import") (part "ElectroSmith_C-EUC0603"))
    )
    (comp (ref "C64")
      (value "0.1uF")
      (footprint "eagle-import:C0603")
      (libsource (lib "eagle-import") (part "ElectroSmith_C-EUC0603"))
    )
    (comp (ref "C65")
      (value "0.1uF")
      (footprint "eagle-import:C0603")
      (libsource (lib "eagle-import") (part "ElectroSmith_C-EUC0603"))
    )
    (comp (ref "C66")
      (value "0.1uF")
      (footprint "eagle-import:C0603")
      (libsource (lib "eagle-import") (part "ElectroSmith_C-EUC0603"))
    )
    (comp (ref "C79")
      (value "0.1uF")
      (footprint "eagle-import:C0603")
      (libsource (lib "eagle-import") (part "ElectroSmith_C-EUC0603"))
    )
    (comp (ref "C80")
      (value "0.1uF")
      (footprint "eagle-import:C0603")
      (libsource (lib "eagle-import") (part "ElectroSmith_C-EUC0603"))
    )
    (comp (ref "J1")
      (value "EURO_JACK")
      (footprint "eagle-import:S_JACK")
      (libsource (lib "eagle-import") (part "EURO_JACK"))
    )
    (comp (ref "J2")
      (value "EURO_JACK")
      (footprint "eagle-import:S_JACK")
      (libsource (lib "eagle-import") (part "EURO_JACK"))
    )
    (comp (ref "J3")
      (value "EURO_JACK")
      (footprint "eagle-import:S_JACK")
      (libsource (lib "eagle-import") (part "EURO_JACK"))
    )
    (comp (ref "J4")
      (value "EURO_JACK")
      (footprint "eagle-import:S_JACK")
      (libsource (lib "eagle-import") (part "EURO_JACK"))
    )
    (comp (ref "J5")
      (value "EURO_JACK")
      (footprint "eagle-import:S_JACK")
      (libsource (lib "eagle-import") (part "EURO_JACK"))
    )
    (comp (ref "J6")
      (value "EURO_JACK")
      (footprint "eagle-import:S_JACK")
      (libsource (lib "eagle-import") (part "EURO_JACK"))
    )
    (comp (ref "J7")
      (value "EURO_JACK")
      (footprint "eagle-import:S_JACK")
      (libsource (lib "eagle-import") (part "EURO_JACK"))
    )
    (comp (ref "J8")
      (value "EURO_JACK")
      (footprint "eagle-import:S_JACK")
      (libsource (lib "eagle-import") (part "EURO_JACK"))
    )
    (comp (ref "J9")
      (value "EURO_JACK")
      (footprint "eagle-import:S_JACK")
      (libsource (lib "eagle-import") (part "EURO_JACK"))
    )
    (comp (ref "J10")
      (value "EURO_JACK")
      (footprint "eagle-import:S_JACK")
      (libsource (lib "eagle-import") (part "EURO_JACK"))
    )
    (comp (ref "J11")
      (value "EURO_JACK")
      (footprint "eagle-import:S_JACK")
      (libsource (lib "eagle-import") (part "EURO_JACK"))
    )
    (comp (ref "J12")
      (value "EURO_JACK")
      (footprint "eagle-import:S_JACK")
      (libsource (lib "eagle-import") (part "EURO_JACK"))
    )
    (comp (ref "J13")
      (value "EURO_JACK")
      (footprint "eagle-import:S_JACK")
      (libsource (lib "eagle-import") (part "EURO_JACK"))
    )
    (comp (ref "Q1")
      (value "MMBT3904")
      (footprint "eagle-import:SOT23-BEC")
      (libsource (lib "eagle-import") (part "-NPN-SOT23-BECMMBT3904LT1"))
    )
    (comp (ref "Q2")
      (value "MMBT3904")
      (footprint "eagle-import:SOT23-BEC")
      (libsource (lib "eagle-import") (part "-NPN-SOT23-BECMMBT3904LT1"))
    )
    (comp (ref "R3")
      (value "100K")
      (footprint "eagle-import:R0603")
      (libsource (lib "eagle-import") (part "R-US_R0603"))
    )
    (comp (ref "R5")
      (value "200K")
      (footprint "eagle-import:R0603")
      (libsource (lib "eagle-import") (part "R-US_R0603"))
    )
    (comp (ref "R6")
      (value "33k")
      (footprint "eagle-import:R0603")
      (libsource (lib "eagle-import") (part "R-US_R0603"))
    )
    (comp (ref "R7")
      (value "16.5K")
      (footprint "eagle-import:R0603")
      (libsource (lib "eagle-import") (part "R-US_R0603"))
    )
    (comp (ref "R8")
      (value "16.5K")
      (footprint "eagle-import:R0603")
      (libsource (lib "eagle-import") (part "R-US_R0603"))
    )
    (comp (ref "R9")
      (value "100K")
      (footprint "eagle-import:R0603")
      (libsource (lib "eagle-import") (part "R-US_R0603"))
    )
    (comp (ref "R10")
      (value "200K")
      (footprint "eagle-import:R0603")
      (libsource (lib "eagle-import") (part "R-US_R0603"))
    )
    (comp (ref "R11")
      (value "33k")
      (footprint "eagle-import:R0603")
      (libsource (lib "eagle-import") (part "R-US_R0603"))
    )
    (comp (ref "R12")
      (value "16.5K")
      (footprint "eagle-import:R0603")
      (libsource (lib "eagle-import") (part "R-US_R0603"))
    )
    (comp (ref "R13")
      (value "16.5K")
      (footprint "eagle-import:R0603")
      (libsource (lib "eagle-import") (part "R-US_R0603"))
    )
    (comp (ref "R14")
      (value "100K")
      (footprint "eagle-import:R0603")
      (libsource (lib "eagle-import") (part "R-US_R0603"))
    )
    (comp (ref "R15")
      (value "200K")
      (footprint "eagle-import:R0603")
      (libsource (lib "eagle-import") (part "R-US_R0603"))
    )
    (comp (ref "R16")
      (value "33k")
      (footprint "eagle-import:R0603")
      (libsource (lib "eagle-import") (part "R-US_R0603"))
    )
    (comp (ref "R17")
      (value "16.5K")
      (footprint "eagle-import:R0603")
      (libsource (lib "eagle-import") (part "R-US_R0603"))
    )
    (comp (ref "R18")
      (value "16.5K")
      (footprint "eagle-import:R0603")
      (libsource (lib "eagle-import") (part "R-US_R0603"))
    )
    (comp (ref "R19")
      (value "200K")
      (footprint "eagle-import:R0603")
      (libsource (lib "eagle-import") (part "R-US_R0603"))
    )
    (comp (ref "R20")
      (value "100K")
      (footprint "eagle-import:R0603")
      (libsource (lib "eagle-import") (part "R-US_R0603"))
    )
    (comp (ref "R21")
      (value "100K")
      (footprint "eagle-import:R0603")
      (libsource (lib "eagle-import") (part "R-US_R0603"))
    )
    (comp (ref "R22")
      (value "200K")
      (footprint "eagle-import:R0603")
      (libsource (lib "eagle-import") (part "R-US_R0603"))
    )
    (comp (ref "R23")
      (value "33k")
      (footprint "eagle-import:R0603")
      (libsource (lib "eagle-import") (part "R-US_R0603"))
    )
    (comp (ref "R24")
      (value "16.5K")
      (footprint "eagle-import:R0603")
      (libsource (lib "eagle-import") (part "R-US_R0603"))
    )
    (comp (ref "R25")
      (value "16.5K")
      (footprint "eagle-import:R0603")
      (libsource (lib "eagle-import") (part "R-US_R0603"))
    )
    (comp (ref "R26")
      (value "100K")
      (footprint "eagle-import:R0603")
      (libsource (lib "eagle-import") (part "R-US_R0603"))
    )
    (comp (ref "R27")
      (value "200K")
      (footprint "eagle-import:R0603")
      (libsource (lib "eagle-import") (part "R-US_R0603"))
    )
    (comp (ref "R28")
      (value "33k")
      (footprint "eagle-import:R0603")
      (libsource (lib "eagle-import") (part "R-US_R0603"))
    )
    (comp (ref "R29")
      (value "16.5K")
      (footprint "eagle-import:R0603")
      (libsource (lib "eagle-import") (part "R-US_R0603"))
    )
    (comp (ref "R30")
      (value "16.5K")
      (footprint "eagle-import:R0603")
      (libsource (lib "eagle-import") (part "R-US_R0603"))
    )
    (comp (ref "R31")
      (value "16.5K")
      (footprint "eagle-import:R0603")
      (libsource (lib "eagle-import") (part "R-US_R0603"))
    )
    (comp (ref "R32")
      (value "100K")
      (footprint "eagle-import:R0603")
      (libsource (lib "eagle-import") (part "R-US_R0603"))
    )
    (comp (ref "R33")
      (value "16.5K")
      (footprint "eagle-import:R0603")
      (libsource (lib "eagle-import") (part "R-US_R0603"))
    )
    (comp (ref "R34")
      (value "200K")
      (footprint "eagle-import:R0603")
      (libsource (lib "eagle-import") (part "R-US_R0603"))
    )
    (comp (ref "R35")
      (value "33k")
      (footprint "eagle-import:R0603")
      (libsource (lib "eagle-import") (part "R-US_R0603"))
    )
    (comp (ref "R36")
      (value "16.5K")
      (footprint "eagle-import:R0603")
      (libsource (lib "eagle-import") (part "R-US_R0603"))
    )
    (comp (ref "R37")
      (value "33k")
      (footprint "eagle-import:R0603")
      (libsource (lib "eagle-import") (part "R-US_R0603"))
    )
    (comp (ref "R38")
      (value "16.5K")
      (footprint "eagle-import:R0603")
      (libsource (lib "eagle-import") (part "R-US_R0603"))
    )
    (comp (ref "R39")
      (value "100K")
      (footprint "eagle-import:R0603")
      (libsource (lib "eagle-import") (part "R-US_R0603"))
    )
    (comp (ref "R40")
      (value "200K")
      (footprint "eagle-import:R0603")
      (libsource (lib "eagle-import") (part "R-US_R0603"))
    )
    (comp (ref "R41")
      (value "33k")
      (footprint "eagle-import:R0603")
      (libsource (lib "eagle-import") (part "R-US_R0603"))
    )
    (comp (ref "R42")
      (value "16.5K")
      (footprint "eagle-import:R0603")
      (libsource (lib "eagle-import") (part "R-US_R0603"))
    )
    (comp (ref "R43")
      (value "16.5K")
      (footprint "eagle-import:R0603")
      (libsource (lib "eagle-import") (part "R-US_R0603"))
    )
    (comp (ref "R44")
      (value "100K")
      (footprint "eagle-import:R0603")
      (libsource (lib "eagle-import") (part "R-US_R0603"))
    )
    (comp (ref "R45")
      (value "200K")
      (footprint "eagle-import:R0603")
      (libsource (lib "eagle-import") (part "R-US_R0603"))
    )
    (comp (ref "R46")
      (value "33k")
      (footprint "eagle-import:R0603")
      (libsource (lib "eagle-import") (part "R-US_R0603"))
    )
    (comp (ref "R47")
      (value "16.5K")
      (footprint "eagle-import:R0603")
      (libsource (lib "eagle-import") (part "R-US_R0603"))
    )
    (comp (ref "R48")
      (value "16.5K")
      (footprint "eagle-import:R0603")
      (libsource (lib "eagle-import") (part "R-US_R0603"))
    )
    (comp (ref "R49")
      (value "100K")
      (footprint "eagle-import:R0603")
      (libsource (lib "eagle-import") (part "R-US_R0603"))
    )
    (comp (ref "R50")
      (value "180K")
      (footprint "eagle-import:R0603")
      (libsource (lib "eagle-import") (part "R-US_R0603"))
    )
    (comp (ref "R51")
      (value "47K")
      (footprint "eagle-import:R0603")
      (libsource (lib "eagle-import") (part "R-US_R0603"))
    )
    (comp (ref "R52")
      (value "1M")
      (footprint "eagle-import:R0603")
      (libsource (lib "eagle-import") (part "R-US_R0603"))
    )
    (comp (ref "R53")
      (value "100R")
      (footprint "eagle-import:R0603")
      (libsource (lib "eagle-import") (part "R-US_R0603"))
    )
    (comp (ref "R54")
      (value "100K")
      (footprint "eagle-import:R0603")
      (libsource (lib "eagle-import") (part "R-US_R0603"))
    )
    (comp (ref "R55")
      (value "100K")
      (footprint "eagle-import:R0603")
      (libsource (lib "eagle-import") (part "R-US_R0603"))
    )
    (comp (ref "R56")
      (value "100K")
      (footprint "eagle-import:R0603")
      (libsource (lib "eagle-import") (part "R-US_R0603"))
    )
    (comp (ref "R57")
      (value "100K")
      (footprint "eagle-import:R0603")
      (libsource (lib "eagle-import") (part "R-US_R0603"))
    )
    (comp (ref "R111")
      (value "100K")
      (footprint "eagle-import:R0603")
      (libsource (lib "eagle-import") (part "R-US_R0603"))
    )
    (comp (ref "R112")
      (value "200K")
      (footprint "eagle-import:R0603")
      (libsource (lib "eagle-import") (part "R-US_R0603"))
    )
    (comp (ref "U6")
      (value "TL074")
      (footprint "eagle-import:SO14")
      (libsource (lib "eagle-import") (part "QUAD_OPAMPD"))
    )
    (comp (ref "U7")
      (value "TL074")
      (footprint "eagle-import:SO14")
      (libsource (lib "eagle-import") (part "QUAD_OPAMPD"))
    )
    (comp (ref "U9")
      (value "MCP6004")
      (footprint "eagle-import:SO14")
      (libsource (lib "eagle-import") (part "QUAD_OPAMPD"))
    )
    (comp (ref "U10")
      (value "MCP6004")
      (footprint "eagle-import:SO14")
      (libsource (lib "eagle-import") (part "QUAD_OPAMPD"))
    )
    (comp (ref "U11")
      (value "MCP6004")
      (footprint "eagle-import:SO14")
      (libsource (lib "eagle-import") (part "QUAD_OPAMPD"))
    )
    (comp (ref "U16")
      (value "TL072")
      (footprint "eagle-import:SO08_BOXPIN")
      (libsource (lib "eagle-import") (part "DUAL_OPAMP"))
    )
    (comp (ref "VR1")
      (value "10k")
      (footprint "eagle-import:9MM_SNAP-IN_POT_NO_SILK")
      (libsource (lib "eagle-import") (part "POT_9MM_SNAP-IN_"))
    )
    (comp (ref "VR2")
      (value "10k")
      (footprint "eagle-import:9MM_SNAP-IN_POT_NO_SILK")
      (libsource (lib "eagle-import") (part "POT_9MM_SNAP-IN_"))
    )
    (comp (ref "VR3")
      (value "10k")
      (footprint "eagle-import:9MM_SNAP-IN_POT_NO_SILK")
      (libsource (lib "eagle-import") (part "POT_9MM_SNAP-IN_"))
    )
    (comp (ref "VR4")
      (value "10k")
      (footprint "eagle-import:9MM_SNAP-IN_POT_NO_SILK")
      (libsource (lib "eagle-import") (part "POT_9MM_SNAP-IN_"))
    )
    (comp (ref "VR5")
      (value "10k")
      (footprint "eagle-import:9MM_SNAP-IN_POT_NO_SILK")
      (libsource (lib "eagle-import") (part "POT_9MM_SNAP-IN_"))
    )
    (comp (ref "VR6")
      (value "10k")
      (footprint "eagle-import:9MM_SNAP-IN_POT_NO_SILK")
      (libsource (lib "eagle-import") (part "POT_9MM_SNAP-IN_"))
    )
    (comp (ref "VR7")
      (value "10k")
      (footprint "eagle-import:9MM_SNAP-IN_POT_NO_SILK")
      (libsource (lib "eagle-import") (part "POT_9MM_SNAP-IN_"))
    )
    (comp (ref "VR8")
      (value "10k")
      (footprint "eagle-import:9MM_SNAP-IN_POT_NO_SILK")
      (libsource (lib "eagle-import") (part "POT_9MM_SNAP-IN_"))
    )
    (comp (ref "VR9")
      (value "10k")
      (footprint "eagle-import:9MM_SNAP-IN_POT_NO_SILK")
      (libsource (lib "eagle-import") (part "POT_9MM_SNAP-IN_"))
    )
  )
  (nets
    (net (code "1") (name "+3.3V_A") (class "Default")
      (node (ref "C10") (pin "1") (pinfunction "1_1") (pintype "passive"))
      (node (ref "C11") (pin "1") (pinfunction "1_1") (pintype "passive"))
      (node (ref "C12") (pin "P$1") (pinfunction "POS_P$1") (pintype "passive"))
      (node (ref "C56") (pin "1") (pinfunction "1_1") (pintype "passive"))
      (node (ref "C57") (pin "1") (pinfunction "1_1") (pintype "passive"))
      (node (ref "C64") (pin "2") (pinfunction "2_2") (pintype "passive"))
      (node (ref "C65") (pin "2") (pinfunction "2_2") (pintype "passive"))
      (node (ref "C66") (pin "2") (pinfunction "2_2") (pintype "passive"))
      (node (ref "C69") (pin "1") (pinfunction "1_1") (pintype "passive"))
      (node (ref "U10") (pin "4") (pinfunction "V+_4") (pintype "power_in"))
      (node (ref "U11") (pin "4") (pinfunction "V+_4") (pintype "power_in"))
      (node (ref "U17") (pin "16") (pinfunction "VCC_16") (pintype "power_in"))
      (node (ref "U2") (pin "21") (pinfunction "VREF+_21") (pintype "power_in"))
      (node (ref "U2") (pin "22") (pinfunction "VDDA_22") (pintype "power_in"))
      (node (ref "U3") (pin "14") (pinfunction "AVDD_14") (pintype "bidirectional"))
      (node (ref "U3") (pin "8") (pinfunction "HPVDD_8") (pintype "bidirectional"))
      (node (ref "U4") (pin "2") (pinfunction "OUT_2") (pintype "passive"))
      (node (ref "U4") (pin "TAB") (pinfunction "OUT1_TAB") (pintype "passive"))
      (node (ref "U9") (pin "4") (pinfunction "V+_4") (pintype "power_in"))
      (node (ref "VR12") (pin "3") (pinfunction "3_3") (pintype "passive"))
      (node (ref "VR13") (pin "3") (pinfunction "3_3") (pintype "passive"))
      (node (ref "VR14") (pin "3") (pinfunction "3_3") (pintype "passive"))
      (node (ref "VR15") (pin "3") (pinfunction "3_3") (pintype "passive"))
      (node (ref "VR16") (pin "3") (pinfunction "3_3") (pintype "passive"))
      (node (ref "VR17") (pin "3") (pinfunction "3_3") (pintype "passive"))
      (node (ref "VR18") (pin "3") (pinfunction "3_3") (pintype "passive"))
      (node (ref "VR19") (pin "3") (pinfunction "3_3") (pintype "passive"))
      (node (ref "VR20") (pin "3") (pinfunction "3_3") (pintype "passive"))
    )
    (net (code "2") (name "+3.3V_D") (class "Default")
      (node (ref "C13") (pin "1") (pinfunction "1_1") (pintype "passive"))
      (node (ref "C14") (pin "P$1") (pinfunction "POS_P$1") (pintype "passive"))
      (node (ref "C4") (pin "1") (pinfunction "1_1") (pintype "passive"))
      (node (ref "C50") (pin "1") (pinfunction "1_1") (pintype "passive"))
      (node (ref "C51") (pin "1") (pinfunction "1_1") (pintype "passive"))
      (node (ref "C52") (pin "1") (pinfunction "1_1") (pintype "passive"))
      (node (ref "C53") (pin "1") (pinfunction "1_1") (pintype "passive"))
      (node (ref "C54") (pin "1") (pinfunction "1_1") (pintype "passive"))
      (node (ref "C55") (pin "1") (pinfunction "1_1") (pintype "passive"))
      (node (ref "P2") (pin "1") (pinfunction "1_1") (pintype "passive"))
      (node (ref "R1") (pin "2") (pinfunction "2_2") (pintype "passive"))
      (node (ref "R106") (pin "2") (pinfunction "2_2") (pintype "passive"))
      (node (ref "R2") (pin "2") (pinfunction "2_2") (pintype "passive"))
      (node (ref "R55") (pin "2") (pinfunction "2_2") (pintype "passive"))
      (node (ref "R57") (pin "2") (pinfunction "2_2") (pintype "passive"))
      (node (ref "S1") (pin "1") (pinfunction "1_1") (pintype "passive"))
      (node (ref "S2") (pin "1") (pinfunction "1_1") (pintype "passive"))
      (node (ref "S3") (pin "3") (pinfunction "3_3") (pintype "passive"))
      (node (ref "S7") (pin "3") (pinfunction "3_3") (pintype "passive"))
      (node (ref "S8") (pin "3") (pinfunction "3_3") (pintype "passive"))
      (node (ref "S9") (pin "3") (pinfunction "3_3") (pintype "passive"))
      (node (ref "SW4") (pin "B") (pinfunction "S_B") (pintype "passive"))
      (node (ref "SW4") (pin "B'") (pinfunction "S1_B'") (pintype "passive"))
      (node (ref "U1") (pin "2") (pinfunction "OUT_2") (pintype "passive"))
      (node (ref "U1") (pin "TAB") (pinfunction "OUT1_TAB") (pintype "passive"))
      (node (ref "U2") (pin "100") (pinfunction "VDD_100") (pintype "power_in"))
      (node (ref "U2") (pin "11") (pinfunction "VDD_2_11") (pintype "power_in"))
      (node (ref "U2") (pin "19") (pinfunction "VDD_3_19") (pintype "power_in"))
      (node (ref "U2") (pin "28") (pinfunction "VDD_4_28") (pintype "power_in"))
      (node (ref "U2") (pin "50") (pinfunction "VDD_5_50") (pintype "power_in"))
      (node (ref "U2") (pin "75") (pinfunction "VDD_6_75") (pintype "power_in"))
      (node (ref "U3") (pin "1") (pinfunction "DBVDD_1") (pintype "bidirectional"))
      (node (ref "U3") (pin "27") (pinfunction "DCVDD_27") (pintype "bidirectional"))
    )
    (net (code "3") (name "+10V") (class "Default")
      (node (ref "C72") (pin "1") (pinfunction "1_1") (pintype "passive"))
      (node (ref "R105") (pin "2") (pinfunction "2_2") (pintype "passive"))
      (node (ref "U15") (pin "1") (pinfunction "C_1") (pintype "passive"))
      (node (ref "VR10") (pin "3") (pinfunction "3_3") (pintype "passive"))
      (node (ref "VR11") (pin "3") (pinfunction "3_3") (pintype "passive"))
    )
    (net (code "4") (name "+12V") (class "Default")
      (node (ref "C1") (pin "1") (pinfunction "1_1") (pintype "passive"))
      (node (ref "C2") (pin "1") (pinfunction "1_1") (pintype "passive"))
      (node (ref "C58") (pin "2") (pinfunction "2_2") (pintype "passive"))
      (node (ref "C6") (pin "1") (pinfunction "1_1") (pintype "passive"))
      (node (ref "C60") (pin "2") (pinfunction "2_2") (pintype "passive"))
      (node (ref "C61") (pin "2") (pinfunction "2_2") (pintype "passive"))
      (node (ref "C67") (pin "2") (pinfunction "2_2") (pintype "passive"))
      (node (ref "C75") (pin "2") (pinfunction "2_2") (pintype "passive"))
      (node (ref "C76") (pin "2") (pinfunction "2_2") (pintype "passive"))
      (node (ref "C79") (pin "2") (pinfunction "2_2") (pintype "passive"))
      (node (ref "C81") (pin "2") (pinfunction "2_2") (pintype "passive"))
      (node (ref "C9") (pin "1") (pinfunction "1_1") (pintype "passive"))
      (node (ref "D1") (pin "C") (pinfunction "C_C") (pintype "passive"))
      (node (ref "R105") (pin "1") (pinfunction "1_1") (pintype "passive"))
      (node (ref "U1") (pin "3") (pinfunction "IN_3") (pintype "input"))
      (node (ref "U12") (pin "4") (pinfunction "V+_4") (pintype "power_in"))
      (node (ref "U13") (pin "16") (pinfunction "V+_16") (pintype "power_in"))
      (node (ref "U16") (pin "8") (pinfunction "V+_8") (pintype "power_in"))
      (node (ref "U18") (pin "16") (pinfunction "V+_16") (pintype "power_in"))
      (node (ref "U19") (pin "8") (pinfunction "V+_8") (pintype "power_in"))
      (node (ref "U4") (pin "3") (pinfunction "IN_3") (pintype "input"))
      (node (ref "U6") (pin "4") (pinfunction "V+_4") (pintype "power_in"))
      (node (ref "U7") (pin "4") (pinfunction "V+_4") (pintype "power_in"))
      (node (ref "U8") (pin "4") (pinfunction "V+_4") (pintype "power_in"))
    )
    (net (code "5") (name "-10V") (class "Default")
      (node (ref "C22") (pin "1") (pinfunction "1_1") (pintype "passive"))
      (node (ref "R10") (pin "1") (pinfunction "1_1") (pintype "passive"))
      (node (ref "R15") (pin "1") (pinfunction "1_1") (pintype "passive"))
      (node (ref "R19") (pin "1") (pinfunction "1_1") (pintype "passive"))
      (node (ref "R22") (pin "1") (pinfunction "1_1") (pintype "passive"))
      (node (ref "R27") (pin "1") (pinfunction "1_1") (pintype "passive"))
      (node (ref "R34") (pin "1") (pinfunction "1_1") (pintype "passive"))
      (node (ref "R4") (pin "2") (pinfunction "2_2") (pintype "passive"))
      (node (ref "R40") (pin "1") (pinfunction "1_1") (pintype "passive"))
      (node (ref "R45") (pin "1") (pinfunction "1_1") (pintype "passive"))
      (node (ref "R5") (pin "1") (pinfunction "1_1") (pintype "passive"))
      (node (ref "R50") (pin "1") (pinfunction "1_1") (pintype "passive"))
      (node (ref "U5") (pin "2") (pinfunction "A_2") (pintype "passive"))
    )
    (net (code "6") (name "-12V") (class "Default")
      (node (ref "C3") (pin "2") (pinfunction "2_2") (pintype "passive"))
      (node (ref "C59") (pin "1") (pinfunction "1_1") (pintype "passive"))
      (node (ref "C62") (pin "1") (pinfunction "1_1") (pintype "passive"))
      (node (ref "C63") (pin "1") (pinfunction "1_1") (pintype "passive"))
      (node (ref "C68") (pin "1") (pinfunction "1_1") (pintype "passive"))
      (node (ref "C7") (pin "2") (pinfunction "2_2") (pintype "passive"))
      (node (ref "C77") (pin "1") (pinfunction "1_1") (pintype "passive"))
      (node (ref "C78") (pin "1") (pinfunction "1_1") (pintype "passive"))
      (node (ref "C80") (pin "1") (pinfunction "1_1") (pintype "passive"))
      (node (ref "C82") (pin "1") (pinfunction "1_1") (pintype "passive"))
      (node (ref "D2") (pin "A") (pinfunction "A_A") (pintype "passive"))
      (node (ref "R104") (pin "1") (pinfunction "1_1") (pintype "passive"))
      (node (ref "R4") (pin "1") (pinfunction "1_1") (pintype "passive"))
      (node (ref "U12") (pin "11") (pinfunction "V-_11") (pintype "power_in"))
      (node (ref "U13") (pin "9") (pinfunction "V-_9") (pintype "power_in"))
      (node (ref "U16") (pin "4") (pinfunction "V-_4") (pintype "power_in"))
      (node (ref "U18") (pin "9") (pinfunction "V-_9") (pintype "power_in"))
      (node (ref "U19") (pin "4") (pinfunction "V-_4") (pintype "power_in"))
      (node (ref "U6") (pin "11") (pinfunction "V-_11") (pintype "power_in"))
      (node (ref "U7") (pin "11") (pinfunction "V-_11") (pintype "power_in"))
      (node (ref "U8") (pin "11") (pinfunction "V-_11") (pintype "power_in"))
    )
    (net (code "7") (name "ADC_EN") (class "Default")
      (node (ref "U17") (pin "6") (pinfunction "INH_6") (pintype "input"))
      (node (ref "U2") (pin "1") (pinfunction "PE2_1") (pintype "bidirectional"))
    )
    (net (code "8") (name "ADC_POT") (class "Default")
      (node (ref "U17") (pin "3") (pinfunction "X_3") (pintype "bidirectional"))
      (node (ref "U2") (pin "36") (pinfunction "PB1_36") (pintype "bidirectional"))
    )
    (net (code "9") (name "ADC_S0") (class "Default")
      (node (ref "U17") (pin "11") (pinfunction "A_11") (pintype "input"))
      (node (ref "U2") (pin "2") (pinfunction "PE3_2") (pintype "bidirectional"))
    )
    (net (code "10") (name "ADC_S1") (class "Default")
      (node (ref "U17") (pin "10") (pinfunction "B_10") (pintype "input"))
      (node (ref "U2") (pin "3") (pinfunction "PE4_3") (pintype "bidirectional"))
    )
    (net (code "11") (name "ADC_S2") (class "Default")
      (node (ref "U17") (pin "9") (pinfunction "C_9") (pintype "input"))
      (node (ref "U2") (pin "4") (pinfunction "PE5_4") (pintype "bidirectional"))
    )
    (net (code "12") (name "AREF_-2.5") (class "Default")
      (node (ref "C70") (pin "1") (pinfunction "1_1") (pintype "passive"))
      (node (ref "C71") (pin "1") (pinfunction "1_1") (pintype "passive"))
      (node (ref "R104") (pin "2") (pinfunction "2_2") (pintype "passive"))
      (node (ref "R64") (pin "2") (pinfunction "2_2") (pintype "passive"))
      (node (ref "R66") (pin "2") (pinfunction "2_2") (pintype "passive"))
      (node (ref "R73") (pin "2") (pinfunction "2_2") (pintype "passive"))
      (node (ref "R74") (pin "2") (pinfunction "2_2") (pintype "passive"))
      (node (ref "U14") (pin "2") (pinfunction "A_2") (pintype "passive"))
    )
    (net (code "13") (name "AUX_INTERNAL_MOD") (class "Default")
      (node (ref "J2") (pin "NORM") (pinfunction "NORM_NORM") (pintype "passive"))
      (node (ref "R111") (pin "1") (pinfunction "1_1") (pintype "passive"))
      (node (ref "U16") (pin "1") (pinfunction "OUT_1") (pintype "output"))
    )
    (net (code "14") (name "AUX_INTERNAL_MOD_RAW") (class "Default")
      (node (ref "U16") (pin "3") (pinfunction "+IN_3") (pintype "input"))
      (node (ref "U2") (pin "29") (pinfunction "PA4_29") (pintype "bidirectional"))
    )
    (net (code "15") (name "AUX_NORMAL") (class "Default")
      (node (ref "J1") (pin "NORM") (pinfunction "NORM_NORM") (pintype "passive"))
      (node (ref "J10") (pin "NORM") (pinfunction "NORM_NORM") (pintype "passive"))
      (node (ref "J3") (pin "NORM") (pinfunction "NORM_NORM") (pintype "passive"))
      (node (ref "J4") (pin "NORM") (pinfunction "NORM_NORM") (pintype "passive"))
      (node (ref "J5") (pin "NORM") (pinfunction "NORM_NORM") (pintype "passive"))
      (node (ref "J6") (pin "NORM") (pinfunction "NORM_NORM") (pintype "passive"))
      (node (ref "J7") (pin "NORM") (pinfunction "NORM_NORM") (pintype "passive"))
      (node (ref "J8") (pin "NORM") (pinfunction "NORM_NORM") (pintype "passive"))
      (node (ref "J9") (pin "NORM") (pinfunction "NORM_NORM") (pintype "passive"))
      (node (ref "R53") (pin "1") (pinfunction "1_1") (pintype "passive"))
    )
    (net (code "16") (name "BOOT_FLASH") (class "Default")
      (node (ref "R107") (pin "2") (pinfunction "2_2") (pintype "passive"))
      (node (ref "SW4") (pin "A") (pinfunction "P_A") (pintype "passive"))
      (node (ref "SW4") (pin "A'") (pinfunction "P1_A'") (pintype "passive"))
      (node (ref "U2") (pin "94") (pinfunction "BOOT0_94") (pintype "input"))
    )
    (net (code "17") (name "CV_VCA_OUT_LEVEL") (class "Default")
      (node (ref "C37") (pin "2") (pinfunction "2_2") (pintype "passive"))
      (node (ref "U13") (pin "11") (pinfunction "CTRL_11") (pintype "input"))
      (node (ref "U13") (pin "3") (pinfunction "CTRL_3") (pintype "input"))
      (node (ref "U18") (pin "14") (pinfunction "CTRL_14") (pintype "input"))
      (node (ref "U2") (pin "33") (pinfunction "PC4_33") (pintype "bidirectional"))
      (node (ref "U8") (pin "8") (pinfunction "OUT_8") (pintype "output"))
    )
    (net (code "18") (name "DENSITY_CV") (class "Default")
      (node (ref "C17") (pin "2") (pinfunction "2_2") (pintype "passive"))
      (node (ref "R16") (pin "2") (pinfunction "2_2") (pintype "passive"))
      (node (ref "U2") (pin "26") (pinfunction "PA3_26") (pintype "bidirectional"))
      (node (ref "U9") (pin "14") (pinfunction "OUT_14") (pintype "output"))
    )
    (net (code "19") (name "DENSITY_POT") (class "Default")
      (node (ref "U17") (pin "4") (pinfunction "X7_4") (pintype "bidirectional"))
      (node (ref "VR19") (pin "2") (pinfunction "2_2") (pintype "passive"))
    )
    (net (code "20") (name "FEEDBACK_CV") (class "Default")
      (node (ref "C20") (pin "2") (pinfunction "2_2") (pintype "passive"))
      (node (ref "R23") (pin "2") (pinfunction "2_2") (pintype "passive"))
      (node (ref "U10") (pin "7") (pinfunction "OUT_7") (pintype "output"))
      (node (ref "U2") (pin "31") (pinfunction "PA6_31") (pintype "bidirectional"))
    )
    (net (code "21") (name "FEEDBACK_POT") (class "Default")
      (node (ref "U17") (pin "14") (pinfunction "X1_14") (pintype "bidirectional"))
      (node (ref "VR16") (pin "2") (pinfunction "2_2") (pintype "passive"))
    )
    (net (code "22") (name "GATE_HOLD") (class "Default")
      (node (ref "Q1") (pin "C") (pinfunction "C_C") (pintype "passive"))
      (node (ref "R55") (pin "1") (pinfunction "1_1") (pintype "passive"))
      (node (ref "U2") (pin "44") (pinfunction "PE13_44") (pintype "bidirectional"))
    )
    (net (code "23") (name "GATE_TRIG") (class "Default")
      (node (ref "Q2") (pin "C") (pinfunction "C_C") (pintype "passive"))
      (node (ref "R57") (pin "1") (pinfunction "1_1") (pintype "passive"))
      (node (ref "U2") (pin "45") (pinfunction "PE14_45") (pintype "bidirectional"))
    )
    (net (code "24") (name "GND") (class "Default")
      (node (ref "C1") (pin "2") (pinfunction "2_2") (pintype "passive"))
      (node (ref "C10") (pin "2") (pinfunction "2_2") (pintype "passive"))
      (node (ref "C11") (pin "2") (pinfunction "2_2") (pintype "passive"))
      (node (ref "C12") (pin "P$2") (pinfunction "NEG_P$2") (pintype "passive"))
      (node (ref "C13") (pin "2") (pinfunction "2_2") (pintype "passive"))
      (node (ref "C14") (pin "P$2") (pinfunction "NEG_P$2") (pintype "passive"))
      (node (ref "C18") (pin "1") (pinfunction "1_1") (pintype "passive"))
      (node (ref "C19") (pin "1") (pinfunction "1_1") (pintype "passive"))
      (node (ref "C2") (pin "2") (pinfunction "2_2") (pintype "passive"))
      (node (ref "C22") (pin "2") (pinfunction "2_2") (pintype "passive"))
      (node (ref "C27") (pin "2") (pinfunction "2_2") (pintype "passive"))
      (node (ref "C28") (pin "2") (pinfunction "2_2") (pintype "passive"))
      (node (ref "C29") (pin "2") (pinfunction "2_2") (pintype "passive"))
      (node (ref "C3") (pin "1") (pinfunction "1_1") (pintype "passive"))
      (node (ref "C33") (pin "1") (pinfunction "1_1") (pintype "passive"))
      (node (ref "C36") (pin "2") (pinfunction "2_2") (pintype "passive"))
      (node (ref "C4") (pin "2") (pinfunction "2_2") (pintype "passive"))
      (node (ref "C40") (pin "2") (pinfunction "2_2") (pintype "passive"))
      (node (ref "C41") (pin "2") (pinfunction "2_2") (pintype "passive"))
      (node (ref "C44") (pin "1") (pinfunction "1_1") (pintype "passive"))
      (node (ref "C46") (pin "1") (pinfunction "1_1") (pintype "passive"))
      (node (ref "C47") (pin "1") (pinfunction "1_1") (pintype "passive"))
      (node (ref "C48") (pin "1") (pinfunction "1_1") (pintype "passive"))
      (node (ref "C49") (pin "1") (pinfunction "1_1") (pintype "passive"))
      (node (ref "C5") (pin "2") (pinfunction "2_2") (pintype "passive"))
      (node (ref "C50") (pin "2") (pinfunction "2_2") (pintype "passive"))
      (node (ref "C51") (pin "2") (pinfunction "2_2") (pintype "passive"))
      (node (ref "C52") (pin "2") (pinfunction "2_2") (pintype "passive"))
      (node (ref "C53") (pin "2") (pinfunction "2_2") (pintype "passive"))
      (node (ref "C54") (pin "2") (pinfunction "2_2") (pintype "passive"))
      (node (ref "C55") (pin "2") (pinfunction "2_2") (pintype "passive"))
      (node (ref "C56") (pin "2") (pinfunction "2_2") (pintype "passive"))
      (node (ref "C57") (pin "2") (pinfunction "2_2") (pintype "passive"))
      (node (ref "C58") (pin "1") (pinfunction "1_1") (pintype "passive"))
      (node (ref "C59") (pin "2") (pinfunction "2_2") (pintype "passive"))
      (node (ref "C6") (pin "2") (pinfunction "2_2") (pintype "passive"))
      (node (ref "C60") (pin "1") (pinfunction "1_1") (pintype "passive"))
      (node (ref "C61") (pin "1") (pinfunction "1_1") (pintype "passive"))
      (node (ref "C62") (pin "2") (pinfunction "2_2") (pintype "passive"))
      (node (ref "C63") (pin "2") (pinfunction "2_2") (pintype "passive"))
      (node (ref "C64") (pin "1") (pinfunction "1_1") (pintype "passive"))
      (node (ref "C65") (pin "1") (pinfunction "1_1") (pintype "passive"))
      (node (ref "C66") (pin "1") (pinfunction "1_1") (pintype "passive"))
      (node (ref "C67") (pin "1") (pinfunction "1_1") (pintype "passive"))
      (node (ref "C68") (pin "2") (pinfunction "2_2") (pintype "passive"))
      (node (ref "C69") (pin "2") (pinfunction "2_2") (pintype "passive"))
      (node (ref "C7") (pin "1") (pinfunction "1_1") (pintype "passive"))
      (node (ref "C70") (pin "2") (pinfunction "2_2") (pintype "passive"))
      (node (ref "C71") (pin "2") (pinfunction "2_2") (pintype "passive"))
      (node (ref "C72") (pin "2") (pinfunction "2_2") (pintype "passive"))
      (node (ref "C73") (pin "2") (pinfunction "2_2") (pintype "passive"))
      (node (ref "C74") (pin "2") (pinfunction "2_2") (pintype "passive"))
      (node (ref "C75") (pin "1") (pinfunction "1_1") (pintype "passive"))
      (node (ref "C76") (pin "1") (pinfunction "1_1") (pintype "passive"))
      (node (ref "C77") (pin "2") (pinfunction "2_2") (pintype "passive"))
      (node (ref "C78") (pin "2") (pinfunction "2_2") (pintype "passive"))
      (node (ref "C79") (pin "1") (pinfunction "1_1") (pintype "passive"))
      (node (ref "C8") (pin "P$2") (pinfunction "NEG_P$2") (pintype "passive"))
      (node (ref "C80") (pin "2") (pinfunction "2_2") (pintype "passive"))
      (node (ref "C81") (pin "1") (pinfunction "1_1") (pintype "passive"))
      (node (ref "C82") (pin "2") (pinfunction "2_2") (pintype "passive"))
      (node (ref "C9") (pin "2") (pinfunction "2_2") (pintype "passive"))
      (node (ref "J1") (pin "GND") (pinfunction "GND_GND") (pintype "passive"))
      (node (ref "J10") (pin "GND") (pinfunction "GND_GND") (pintype "passive"))
      (node (ref "J11") (pin "GND") (pinfunction "GND_GND") (pintype "passive"))
      (node (ref "J12") (pin "GND") (pinfunction "GND_GND") (pintype "passive"))
      (node (ref "J12") (pin "NORM") (pinfunction "NORM_NORM") (pintype "passive"))
      (node (ref "J13") (pin "GND") (pinfunction "GND_GND") (pintype "passive"))
      (node (ref "J13") (pin "NORM") (pinfunction "NORM_NORM") (pintype "passive"))
      (node (ref "J14") (pin "GND") (pinfunction "GND_GND") (pintype "passive"))
      (node (ref "J15") (pin "GND") (pinfunction "GND_GND") (pintype "passive"))
      (node (ref "J16") (pin "GND") (pinfunction "GND_GND") (pintype "passive"))
      (node (ref "J17") (pin "GND") (pinfunction "GND_GND") (pintype "passive"))
      (node (ref "J18") (pin "GND") (pinfunction "GND_GND") (pintype "passive"))
      (node (ref "J19") (pin "GND") (pinfunction "GND_GND") (pintype "passive"))
      (node (ref "J2") (pin "GND") (pinfunction "GND_GND") (pintype "passive"))
      (node (ref "J3") (pin "GND") (pinfunction "GND_GND") (pintype "passive"))
      (node (ref "J4") (pin "GND") (pinfunction "GND_GND") (pintype "passive"))
      (node (ref "J5") (pin "GND") (pinfunction "GND_GND") (pintype "passive"))
      (node (ref "J6") (pin "GND") (pinfunction "GND_GND") (pintype "passive"))
      (node (ref "J7") (pin "GND") (pinfunction "GND_GND") (pintype "passive"))
      (node (ref "J8") (pin "GND") (pinfunction "GND_GND") (pintype "passive"))
      (node (ref "J9") (pin "GND") (pinfunction "GND_GND") (pintype "passive"))
      (node (ref "JP1") (pin "1") (pinfunction "1_1") (pintype "passive"))
      (node (ref "LED1") (pin "K") (pinfunction "C_K") (pintype "passive"))
      (node (ref "LED10") (pin "K") (pinfunction "C_K") (pintype "passive"))
      (node (ref "LED11") (pin "K") (pinfunction "C_K") (pintype "passive"))
      (node (ref "LED12") (pin "K") (pinfunction "C_K") (pintype "passive"))
      (node (ref "LED13") (pin "K") (pinfunction "C_K") (pintype "passive"))
      (node (ref "LED14") (pin "K") (pinfunction "C_K") (pintype "passive"))
      (node (ref "LED15") (pin "K") (pinfunction "C_K") (pintype "passive"))
      (node (ref "LED16") (pin "K") (pinfunction "C_K") (pintype "passive"))
      (node (ref "LED17") (pin "K") (pinfunction "C_K") (pintype "passive"))
      (node (ref "LED2") (pin "K") (pinfunction "C_K") (pintype "passive"))
      (node (ref "LED3") (pin "K") (pinfunction "C_K") (pintype "passive"))
      (node (ref "LED4") (pin "K") (pinfunction "C_K") (pintype "passive"))
      (node (ref "LED5") (pin "K") (pinfunction "C_K") (pintype "passive"))
      (node (ref "LED6") (pin "K") (pinfunction "C_K") (pintype "passive"))
      (node (ref "LED7") (pin "K") (pinfunction "C_K") (pintype "passive"))
      (node (ref "LED8") (pin "K") (pinfunction "C_K") (pintype "passive"))
      (node (ref "LED9") (pin "K") (pinfunction "C_K") (pintype "passive"))
      (node (ref "P1") (pin "GND1") (pinfunction "4_GND1") (pintype "bidirectional"))
      (node (ref "P1") (pin "GND2") (pinfunction "3_GND2") (pintype "bidirectional"))
      (node (ref "P1") (pin "GND3") (pinfunction "6_GND3") (pintype "bidirectional"))
      (node (ref "P1") (pin "GND4") (pinfunction "5_GND4") (pintype "bidirectional"))
      (node (ref "P1") (pin "GND5") (pinfunction "8_GND5") (pintype "bidirectional"))
      (node (ref "P1") (pin "GND6") (pinfunction "7_GND6") (pintype "bidirectional"))
      (node (ref "P2") (pin "3") (pinfunction "3_3") (pintype "passive"))
      (node (ref "P2") (pin "5") (pinfunction "5_5") (pintype "passive"))
      (node (ref "P2") (pin "9") (pinfunction "9_9") (pintype "passive"))
      (node (ref "Q1") (pin "E") (pinfunction "E_E") (pintype "passive"))
      (node (ref "Q2") (pin "E") (pinfunction "E_E") (pintype "passive"))
      (node (ref "R107") (pin "1") (pinfunction "1_1") (pintype "passive"))
      (node (ref "R112") (pin "2") (pinfunction "2_2") (pintype "passive"))
      (node (ref "R113") (pin "2") (pinfunction "2_2") (pintype "passive"))
      (node (ref "R115") (pin "2") (pinfunction "2_2") (pintype "passive"))
      (node (ref "R52") (pin "1") (pinfunction "1_1") (pintype "passive"))
      (node (ref "R71") (pin "2") (pinfunction "2_2") (pintype "passive"))
      (node (ref "R82") (pin "2") (pinfunction "2_2") (pintype "passive"))
      (node (ref "R86") (pin "2") (pinfunction "2_2") (pintype "passive"))
      (node (ref "R87") (pin "2") (pinfunction "2_2") (pintype "passive"))
      (node (ref "SW5") (pin "A") (pinfunction "P_A") (pintype "passive"))
      (node (ref "SW5") (pin "A'") (pinfunction "P1_A'") (pintype "passive"))
      (node (ref "U1") (pin "1") (pinfunction "GND_1") (pintype "input"))
      (node (ref "U10") (pin "10") (pinfunction "+IN_10") (pintype "input"))
      (node (ref "U10") (pin "11") (pinfunction "V-_11") (pintype "power_in"))
      (node (ref "U10") (pin "12") (pinfunction "+IN_12") (pintype "input"))
      (node (ref "U10") (pin "3") (pinfunction "+IN_3") (pintype "input"))
      (node (ref "U10") (pin "5") (pinfunction "+IN_5") (pintype "input"))
      (node (ref "U11") (pin "10") (pinfunction "+IN_10") (pintype "input"))
      (node (ref "U11") (pin "11") (pinfunction "V-_11") (pintype "power_in"))
      (node (ref "U11") (pin "12") (pinfunction "+IN_12") (pintype "input"))
      (node (ref "U11") (pin "3") (pinfunction "+IN_3") (pintype "input"))
      (node (ref "U11") (pin "5") (pinfunction "+IN_5") (pintype "input"))
      (node (ref "U12") (pin "10") (pinfunction "+IN_10") (pintype "input"))
      (node (ref "U12") (pin "12") (pinfunction "+IN_12") (pintype "input"))
      (node (ref "U12") (pin "3") (pinfunction "+IN_3") (pintype "input"))
      (node (ref "U12") (pin "5") (pinfunction "+IN_5") (pintype "input"))
      (node (ref "U13") (pin "8") (pinfunction "GND_8") (pintype "power_in"))
      (node (ref "U14") (pin "1") (pinfunction "C_1") (pintype "passive"))
      (node (ref "U15") (pin "2") (pinfunction "A_2") (pintype "passive"))
      (node (ref "U16") (pin "5") (pinfunction "+IN_5") (pintype "input"))
      (node (ref "U17") (pin "7") (pinfunction "VEE_7") (pintype "power_in"))
      (node (ref "U17") (pin "8") (pinfunction "GND_8") (pintype "power_in"))
      (node (ref "U18") (pin "8") (pinfunction "GND_8") (pintype "power_in"))
      (node (ref "U2") (pin "10") (pinfunction "VSS_2_10") (pintype "power_in"))
      (node (ref "U2") (pin "20") (pinfunction "VSSA_20") (pintype "power_in"))
      (node (ref "U2") (pin "27") (pinfunction "VSS_3_27") (pintype "power_in"))
      (node (ref "U2") (pin "74") (pinfunction "VSS_4_74") (pintype "power_in"))
      (node (ref "U2") (pin "99") (pinfunction "VSS_99") (pintype "power_in"))
      (node (ref "U3") (pin "11") (pinfunction "HPGND_11") (pintype "bidirectional"))
      (node (ref "U3") (pin "15") (pinfunction "AGND_15") (pintype "bidirectional"))
      (node (ref "U3") (pin "21") (pinfunction "MODE_21") (pintype "bidirectional"))
      (node (ref "U3") (pin "22") (pinfunction "CSB_22") (pintype "bidirectional"))
      (node (ref "U3") (pin "28") (pinfunction "DGND_28") (pintype "bidirectional"))
      (node (ref "U4") (pin "1") (pinfunction "GND_1") (pintype "input"))
      (node (ref "U5") (pin "1") (pinfunction "C_1") (pintype "passive"))
      (node (ref "U6") (pin "10") (pinfunction "+IN_10") (pintype "input"))
      (node (ref "U6") (pin "12") (pinfunction "+IN_12") (pintype "input"))
      (node (ref "U6") (pin "3") (pinfunction "+IN_3") (pintype "input"))
      (node (ref "U6") (pin "5") (pinfunction "+IN_5") (pintype "input"))
      (node (ref "U7") (pin "10") (pinfunction "+IN_10") (pintype "input"))
      (node (ref "U7") (pin "12") (pinfunction "+IN_12") (pintype "input"))
      (node (ref "U7") (pin "3") (pinfunction "+IN_3") (pintype "input"))
      (node (ref "U7") (pin "5") (pinfunction "+IN_5") (pintype "input"))
      (node (ref "U8") (pin "10") (pinfunction "+IN_10") (pintype "input"))
      (node (ref "U8") (pin "12") (pinfunction "+IN_12") (pintype "input"))
      (node (ref "U8") (pin "3") (pinfunction "+IN_3") (pintype "input"))
      (node (ref "U9") (pin "10") (pinfunction "+IN_10") (pintype "input"))
      (node (ref "U9") (pin "11") (pinfunction "V-_11") (pintype "power_in"))
      (node (ref "U9") (pin "12") (pinfunction "+IN_12") (pintype "input"))
      (node (ref "U9") (pin "3") (pinfunction "+IN_3") (pintype "input"))
      (node (ref "U9") (pin "5") (pinfunction "+IN_5") (pintype "input"))
      (node (ref "VR10") (pin "1") (pinfunction "1_1") (pintype "passive"))
      (node (ref "VR11") (pin "1") (pinfunction "1_1") (pintype "passive"))
      (node (ref "VR12") (pin "1") (pinfunction "1_1") (pintype "passive"))
      (node (ref "VR13") (pin "1") (pinfunction "1_1") (pintype "passive"))
      (node (ref "VR14") (pin "1") (pinfunction "1_1") (pintype "passive"))
      (node (ref "VR15") (pin "1") (pinfunction "1_1") (pintype "passive"))
      (node (ref "VR16") (pin "1") (pinfunction "1_1") (pintype "passive"))
      (node (ref "VR17") (pin "1") (pinfunction "1_1") (pintype "passive"))
      (node (ref "VR18") (pin "1") (pinfunction "1_1") (pintype "passive"))
      (node (ref "VR19") (pin "1") (pinfunction "1_1") (pintype "passive"))
      (node (ref "VR20") (pin "1") (pinfunction "1_1") (pintype "passive"))
    )
    (net (code "25") (name "I2C_SCL") (class "Default")
      (node (ref "R1") (pin "1") (pinfunction "1_1") (pintype "passive"))
      (node (ref "U2") (pin "47") (pinfunction "PB10_47") (pintype "bidirectional"))
      (node (ref "U3") (pin "24") (pinfunction "SCLK_24") (pintype "bidirectional"))
    )
    (net (code "26") (name "I2C_SDA") (class "Default")
      (node (ref "R2") (pin "1") (pinfunction "1_1") (pintype "passive"))
      (node (ref "U2") (pin "48") (pinfunction "PB11_48") (pintype "bidirectional"))
      (node (ref "U3") (pin "23") (pinfunction "SDIN_23") (pintype "bidirectional"))
    )
    (net (code "27") (name "I2S_LRCK") (class "Default")
      (node (ref "U2") (pin "51") (pinfunction "PB12_51") (pintype "bidirectional"))
      (node (ref "U3") (pin "5") (pinfunction "DACLRC_5") (pintype "bidirectional"))
      (node (ref "U3") (pin "7") (pinfunction "ADCLRC_7") (pintype "bidirectional"))
    )
    (net (code "28") (name "I2S_SCK") (class "Default")
      (node (ref "U2") (pin "52") (pinfunction "PB13_52") (pintype "bidirectional"))
      (node (ref "U3") (pin "3") (pinfunction "BCLK_3") (pintype "bidirectional"))
    )
    (net (code "29") (name "I2S_SIN") (class "Default")
      (node (ref "U2") (pin "53") (pinfunction "PB14_53") (pintype "bidirectional"))
      (node (ref "U3") (pin "6") (pinfunction "ADCDAT_6") (pintype "bidirectional"))
    )
    (net (code "30") (name "I2S_SOUT") (class "Default")
      (node (ref "U2") (pin "54") (pinfunction "PB15_54") (pintype "bidirectional"))
      (node (ref "U3") (pin "4") (pinfunction "DACDAT_4") (pintype "bidirectional"))
    )
    (net (code "31") (name "JTCK") (class "Default")
      (node (ref "P2") (pin "4") (pinfunction "4_4") (pintype "passive"))
      (node (ref "U2") (pin "76") (pinfunction "PA14_76") (pintype "bidirectional"))
    )
    (net (code "32") (name "JTDI") (class "Default")
      (node (ref "P2") (pin "8") (pinfunction "8_8") (pintype "passive"))
      (node (ref "U2") (pin "77") (pinfunction "PA15_77") (pintype "bidirectional"))
    )
    (net (code "33") (name "JTDO") (class "Default")
      (node (ref "P2") (pin "6") (pinfunction "6_6") (pintype "passive"))
      (node (ref "U2") (pin "89") (pinfunction "PB3_89") (pintype "bidirectional"))
    )
    (net (code "34") (name "JTMS") (class "Default")
      (node (ref "P2") (pin "2") (pinfunction "2_2") (pintype "passive"))
      (node (ref "U2") (pin "72") (pinfunction "PA13_72") (pintype "bidirectional"))
    )
    (net (code "35") (name "LED_BANK_1") (class "Default")
      (node (ref "R100") (pin "2") (pinfunction "2_2") (pintype "passive"))
      (node (ref "U2") (pin "85") (pinfunction "PD4_85") (pintype "bidirectional"))
    )
    (net (code "36") (name "LED_BANK_2") (class "Default")
      (node (ref "R101") (pin "2") (pinfunction "2_2") (pintype "passive"))
      (node (ref "U2") (pin "86") (pinfunction "PD5_86") (pintype "bidirectional"))
    )
    (net (code "37") (name "LED_BANK_3") (class "Default")
      (node (ref "R102") (pin "2") (pinfunction "2_2") (pintype "passive"))
      (node (ref "U2") (pin "87") (pinfunction "PD6_87") (pintype "bidirectional"))
    )
    (net (code "38") (name "LED_BANK_4") (class "Default")
      (node (ref "R103") (pin "2") (pinfunction "2_2") (pintype "passive"))
      (node (ref "U2") (pin "88") (pinfunction "PD7_88") (pintype "bidirectional"))
    )
    (net (code "39") (name "LED_HOLD") (class "Default")
      (node (ref "R108") (pin "2") (pinfunction "2_2") (pintype "passive"))
      (node (ref "U2") (pin "57") (pinfunction "PD10_57") (pintype "bidirectional"))
    )
    (net (code "40") (name "LED_TIME_1") (class "Default")
      (node (ref "R96") (pin "2") (pinfunction "2_2") (pintype "passive"))
      (node (ref "U2") (pin "81") (pinfunction "PD0_81") (pintype "bidirectional"))
    )
    (net (code "41") (name "LED_TIME_2") (class "Default")
      (node (ref "R97") (pin "2") (pinfunction "2_2") (pintype "passive"))
      (node (ref "U2") (pin "82") (pinfunction "PD1_82") (pintype "bidirectional"))
    )
    (net (code "42") (name "LED_TIME_3") (class "Default")
      (node (ref "R98") (pin "2") (pinfunction "2_2") (pintype "passive"))
      (node (ref "U2") (pin "83") (pinfunction "PD2_83") (pintype "bidirectional"))
    )
    (net (code "43") (name "LED_TIME_4") (class "Default")
      (node (ref "R99") (pin "2") (pinfunction "2_2") (pintype "passive"))
      (node (ref "U2") (pin "84") (pinfunction "PD3_84") (pintype "bidirectional"))
    )
    (net (code "44") (name "LIN") (class "Default")
      (node (ref "C35") (pin "P$1") (pinfunction "POS_P$1") (pintype "passive"))
      (node (ref "U3") (pin "20") (pinfunction "LLINEIN_20") (pintype "bidirectional"))
    )
    (net (code "45") (name "LOUT") (class "Default")
      (node (ref "C42") (pin "P$1") (pinfunction "POS_P$1") (pintype "passive"))
      (node (ref "U3") (pin "12") (pinfunction "LOUT_12") (pintype "bidirectional"))
    )
    (net (code "46") (name "MIX_CV") (class "Default")
      (node (ref "C23") (pin "2") (pinfunction "2_2") (pintype "passive"))
      (node (ref "R35") (pin "2") (pinfunction "2_2") (pintype "passive"))
      (node (ref "U10") (pin "14") (pinfunction "OUT_14") (pintype "output"))
      (node (ref "U2") (pin "35") (pinfunction "PB0_35") (pintype "bidirectional"))
    )
    (net (code "47") (name "MIX_POT") (class "Default")
      (node (ref "U17") (pin "12") (pinfunction "X3_12") (pintype "bidirectional"))
      (node (ref "VR17") (pin "2") (pinfunction "2_2") (pintype "passive"))
    )
    (net (code "48") (name "Net-(C8-POS)") (class "Default")
      (node (ref "C5") (pin "1") (pinfunction "1_1") (pintype "passive"))
      (node (ref "C8") (pin "P$1") (pinfunction "POS_P$1") (pintype "passive"))
      (node (ref "U3") (pin "16") (pinfunction "VMID_16") (pintype "bidirectional"))
    )
    (net (code "49") (name "Net-(C27-Pad1)") (class "Default")
      (node (ref "C27") (pin "1") (pinfunction "1_1") (pintype "passive"))
      (node (ref "R58") (pin "1") (pinfunction "1_1") (pintype "passive"))
    )
    (net (code "50") (name "Net-(C28-Pad1)") (class "Default")
      (node (ref "C28") (pin "1") (pinfunction "1_1") (pintype "passive"))
      (node (ref "R59") (pin "1") (pinfunction "1_1") (pintype "passive"))
    )
    (net (code "51") (name "Net-(C29-Pad1)") (class "Default")
      (node (ref "C29") (pin "1") (pinfunction "1_1") (pintype "passive"))
      (node (ref "R63") (pin "1") (pinfunction "1_1") (pintype "passive"))
    )
    (net (code "52") (name "Net-(C35-NEG)") (class "Default")
      (node (ref "C33") (pin "2") (pinfunction "2_2") (pintype "passive"))
      (node (ref "C35") (pin "P$2") (pinfunction "NEG_P$2") (pintype "passive"))
      (node (ref "R65") (pin "1") (pinfunction "1_1") (pintype "passive"))
      (node (ref "R71") (pin "1") (pinfunction "1_1") (pintype "passive"))
    )
    (net (code "53") (name "Net-(C36-Pad1)") (class "Default")
      (node (ref "C36") (pin "1") (pinfunction "1_1") (pintype "passive"))
      (node (ref "R72") (pin "1") (pinfunction "1_1") (pintype "passive"))
    )
    (net (code "54") (name "Net-(C40-Pad1)") (class "Default")
      (node (ref "C40") (pin "1") (pinfunction "1_1") (pintype "passive"))
      (node (ref "R85") (pin "1") (pinfunction "1_1") (pintype "passive"))
    )
    (net (code "55") (name "Net-(C41-Pad1)") (class "Default")
      (node (ref "C41") (pin "1") (pinfunction "1_1") (pintype "passive"))
      (node (ref "R81") (pin "1") (pinfunction "1_1") (pintype "passive"))
    )
    (net (code "56") (name "Net-(C42-NEG)") (class "Default")
      (node (ref "C42") (pin "P$2") (pinfunction "NEG_P$2") (pintype "passive"))
      (node (ref "R80") (pin "2") (pinfunction "2_2") (pintype "passive"))
      (node (ref "R82") (pin "1") (pinfunction "1_1") (pintype "passive"))
    )
    (net (code "57") (name "Net-(C43-NEG)") (class "Default")
      (node (ref "C43") (pin "P$2") (pinfunction "NEG_P$2") (pintype "passive"))
      (node (ref "R84") (pin "2") (pinfunction "2_2") (pintype "passive"))
      (node (ref "R86") (pin "1") (pinfunction "1_1") (pintype "passive"))
    )
    (net (code "58") (name "Net-(C45-NEG)") (class "Default")
      (node (ref "C44") (pin "2") (pinfunction "2_2") (pintype "passive"))
      (node (ref "C45") (pin "P$2") (pinfunction "NEG_P$2") (pintype "passive"))
      (node (ref "R68") (pin "1") (pinfunction "1_1") (pintype "passive"))
      (node (ref "R87") (pin "1") (pinfunction "1_1") (pintype "passive"))
    )
    (net (code "59") (name "Net-(C73-Pad1)") (class "Default")
      (node (ref "C73") (pin "1") (pinfunction "1_1") (pintype "passive"))
      (node (ref "R109") (pin "1") (pinfunction "1_1") (pintype "passive"))
    )
    (net (code "60") (name "Net-(C74-Pad1)") (class "Default")
      (node (ref "C74") (pin "1") (pinfunction "1_1") (pintype "passive"))
      (node (ref "R110") (pin "1") (pinfunction "1_1") (pintype "passive"))
    )
    (net (code "61") (name "Net-(J1-PadTIP)") (class "Default")
      (node (ref "J1") (pin "TIP") (pinfunction "TIP_TIP") (pintype "passive"))
      (node (ref "R20") (pin "1") (pinfunction "1_1") (pintype "passive"))
    )
    (net (code "62") (name "Net-(J3-PadTIP)") (class "Default")
      (node (ref "J3") (pin "TIP") (pinfunction "TIP_TIP") (pintype "passive"))
      (node (ref "R3") (pin "1") (pinfunction "1_1") (pintype "passive"))
    )
    (net (code "63") (name "Net-(J4-PadTIP)") (class "Default")
      (node (ref "J4") (pin "TIP") (pinfunction "TIP_TIP") (pintype "passive"))
      (node (ref "R9") (pin "1") (pinfunction "1_1") (pintype "passive"))
    )
    (net (code "64") (name "Net-(J5-PadTIP)") (class "Default")
      (node (ref "J5") (pin "TIP") (pinfunction "TIP_TIP") (pintype "passive"))
      (node (ref "R14") (pin "1") (pinfunction "1_1") (pintype "passive"))
    )
    (net (code "65") (name "Net-(J6-PadTIP)") (class "Default")
      (node (ref "J6") (pin "TIP") (pinfunction "TIP_TIP") (pintype "passive"))
      (node (ref "R21") (pin "1") (pinfunction "1_1") (pintype "passive"))
    )
    (net (code "66") (name "Net-(J7-PadTIP)") (class "Default")
      (node (ref "J7") (pin "TIP") (pinfunction "TIP_TIP") (pintype "passive"))
      (node (ref "R26") (pin "1") (pinfunction "1_1") (pintype "passive"))
    )
    (net (code "67") (name "Net-(J8-PadTIP)") (class "Default")
      (node (ref "J8") (pin "TIP") (pinfunction "TIP_TIP") (pintype "passive"))
      (node (ref "R32") (pin "1") (pinfunction "1_1") (pintype "passive"))
    )
    (net (code "68") (name "Net-(J9-PadTIP)") (class "Default")
      (node (ref "J9") (pin "TIP") (pinfunction "TIP_TIP") (pintype "passive"))
      (node (ref "R39") (pin "1") (pinfunction "1_1") (pintype "passive"))
    )
    (net (code "69") (name "Net-(J10-PadTIP)") (class "Default")
      (node (ref "J10") (pin "TIP") (pinfunction "TIP_TIP") (pintype "passive"))
      (node (ref "R44") (pin "1") (pinfunction "1_1") (pintype "passive"))
    )
    (net (code "70") (name "Net-(J11-PadTIP)") (class "Default")
      (node (ref "J11") (pin "TIP") (pinfunction "TIP_TIP") (pintype "passive"))
      (node (ref "R49") (pin "1") (pinfunction "1_1") (pintype "passive"))
    )
    (net (code "71") (name "Net-(J12-PadTIP)") (class "Default")
      (node (ref "J12") (pin "TIP") (pinfunction "TIP_TIP") (pintype "passive"))
      (node (ref "R54") (pin "1") (pinfunction "1_1") (pintype "passive"))
    )
    (net (code "72") (name "Net-(J13-PadTIP)") (class "Default")
      (node (ref "J13") (pin "TIP") (pinfunction "TIP_TIP") (pintype "passive"))
      (node (ref "R56") (pin "1") (pinfunction "1_1") (pintype "passive"))
    )
    (net (code "73") (name "Net-(J14-PadTIP)") (class "Default")
      (node (ref "J14") (pin "TIP") (pinfunction "TIP_TIP") (pintype "passive"))
      (node (ref "J15") (pin "NORM") (pinfunction "NORM_NORM") (pintype "passive"))
      (node (ref "R61") (pin "2") (pinfunction "2_2") (pintype "passive"))
    )
    (net (code "74") (name "Net-(J15-PadTIP)") (class "Default")
      (node (ref "J15") (pin "TIP") (pinfunction "TIP_TIP") (pintype "passive"))
      (node (ref "R60") (pin "2") (pinfunction "2_2") (pintype "passive"))
    )
    (net (code "75") (name "Net-(J16-PadTIP)") (class "Default")
      (node (ref "J16") (pin "TIP") (pinfunction "TIP_TIP") (pintype "passive"))
      (node (ref "R70") (pin "2") (pinfunction "2_2") (pintype "passive"))
    )
    (net (code "76") (name "Net-(J17-PadTIP)") (class "Default")
      (node (ref "J17") (pin "TIP") (pinfunction "TIP_TIP") (pintype "passive"))
      (node (ref "R76") (pin "2") (pinfunction "2_2") (pintype "passive"))
    )
    (net (code "77") (name "Net-(J18-PadTIP)") (class "Default")
      (node (ref "J18") (pin "TIP") (pinfunction "TIP_TIP") (pintype "passive"))
      (node (ref "R78") (pin "1") (pinfunction "1_1") (pintype "passive"))
    )
    (net (code "78") (name "Net-(J19-PadTIP)") (class "Default")
      (node (ref "J19") (pin "TIP") (pinfunction "TIP_TIP") (pintype "passive"))
      (node (ref "R83") (pin "1") (pinfunction "1_1") (pintype "passive"))
    )
    (net (code "79") (name "Net-(LED1-PadA)") (class "Default")
      (node (ref "LED1") (pin "A") (pinfunction "A_A") (pintype "passive"))
      (node (ref "R88") (pin "1") (pinfunction "1_1") (pintype "passive"))
    )
    (net (code "80") (name "Net-(LED2-PadA)") (class "Default")
      (node (ref "LED2") (pin "A") (pinfunction "A_A") (pintype "passive"))
      (node (ref "R90") (pin "1") (pinfunction "1_1") (pintype "passive"))
    )
    (net (code "81") (name "Net-(LED3-PadA)") (class "Default")
      (node (ref "LED3") (pin "A") (pinfunction "A_A") (pintype "passive"))
      (node (ref "R92") (pin "1") (pinfunction "1_1") (pintype "passive"))
    )
    (net (code "82") (name "Net-(LED4-PadA)") (class "Default")
      (node (ref "LED4") (pin "A") (pinfunction "A_A") (pintype "passive"))
      (node (ref "R94") (pin "1") (pinfunction "1_1") (pintype "passive"))
    )
    (net (code "83") (name "Net-(LED5-PadA)") (class "Default")
      (node (ref "LED5") (pin "A") (pinfunction "A_A") (pintype "passive"))
      (node (ref "R96") (pin "1") (pinfunction "1_1") (pintype "passive"))
    )
    (net (code "84") (name "Net-(LED6-PadA)") (class "Default")
      (node (ref "LED6") (pin "A") (pinfunction "A_A") (pintype "passive"))
      (node (ref "R97") (pin "1") (pinfunction "1_1") (pintype "passive"))
    )
    (net (code "85") (name "Net-(LED7-PadA)") (class "Default")
      (node (ref "LED7") (pin "A") (pinfunction "A_A") (pintype "passive"))
      (node (ref "R98") (pin "1") (pinfunction "1_1") (pintype "passive"))
    )
    (net (code "86") (name "Net-(LED8-PadA)") (class "Default")
      (node (ref "LED8") (pin "A") (pinfunction "A_A") (pintype "passive"))
      (node (ref "R99") (pin "1") (pinfunction "1_1") (pintype "passive"))
    )
    (net (code "87") (name "Net-(LED9-PadA)") (class "Default")
      (node (ref "LED9") (pin "A") (pinfunction "A_A") (pintype "passive"))
      (node (ref "R89") (pin "1") (pinfunction "1_1") (pintype "passive"))
    )
    (net (code "88") (name "Net-(LED10-PadA)") (class "Default")
      (node (ref "LED10") (pin "A") (pinfunction "A_A") (pintype "passive"))
      (node (ref "R91") (pin "1") (pinfunction "1_1") (pintype "passive"))
    )
    (net (code "89") (name "Net-(LED11-PadA)") (class "Default")
      (node (ref "LED11") (pin "A") (pinfunction "A_A") (pintype "passive"))
      (node (ref "R93") (pin "1") (pinfunction "1_1") (pintype "passive"))
    )
    (net (code "90") (name "Net-(LED12-PadA)") (class "Default")
      (node (ref "LED12") (pin "A") (pinfunction "A_A") (pintype "passive"))
      (node (ref "R95") (pin "1") (pinfunction "1_1") (pintype "passive"))
    )
    (net (code "91") (name "Net-(LED13-PadA)") (class "Default")
      (node (ref "LED13") (pin "A") (pinfunction "A_A") (pintype "passive"))
      (node (ref "R100") (pin "1") (pinfunction "1_1") (pintype "passive"))
    )
    (net (code "92") (name "Net-(LED14-PadA)") (class "Default")
      (node (ref "LED14") (pin "A") (pinfunction "A_A") (pintype "passive"))
      (node (ref "R101") (pin "1") (pinfunction "1_1") (pintype "passive"))
    )
    (net (code "93") (name "Net-(LED15-PadA)") (class "Default")
      (node (ref "LED15") (pin "A") (pinfunction "A_A") (pintype "passive"))
      (node (ref "R102") (pin "1") (pinfunction "1_1") (pintype "passive"))
    )
    (net (code "94") (name "Net-(LED16-PadA)") (class "Default")
      (node (ref "LED16") (pin "A") (pinfunction "A_A") (pintype "passive"))
      (node (ref "R103") (pin "1") (pinfunction "1_1") (pintype "passive"))
    )
    (net (code "95") (name "Net-(LED17-PadA)") (class "Default")
      (node (ref "LED17") (pin "A") (pinfunction "A_A") (pintype "passive"))
      (node (ref "R108") (pin "1") (pinfunction "1_1") (pintype "passive"))
    )
    (net (code "96") (name "Net-(P1-1)") (class "Default")
      (node (ref "D2") (pin "C") (pinfunction "C_C") (pintype "passive"))
      (node (ref "P1") (pin "NEG1") (pinfunction "2_NEG1") (pintype "bidirectional"))
      (node (ref "P1") (pin "NEG2") (pinfunction "1_NEG2") (pintype "bidirectional"))
    )
    (net (code "97") (name "Net-(P1-10)") (class "Default")
      (node (ref "D1") (pin "A") (pinfunction "A_A") (pintype "passive"))
      (node (ref "P1") (pin "POS1") (pinfunction "10_POS1") (pintype "bidirectional"))
      (node (ref "P1") (pin "POS2") (pinfunction "9_POS2") (pintype "bidirectional"))
    )
    (net (code "98") (name "Net-(Q1-PadB)") (class "Default")
      (node (ref "Q1") (pin "B") (pinfunction "B_B") (pintype "passive"))
      (node (ref "R54") (pin "2") (pinfunction "2_2") (pintype "passive"))
    )
    (net (code "99") (name "Net-(Q2-PadB)") (class "Default")
      (node (ref "Q2") (pin "B") (pinfunction "B_B") (pintype "passive"))
      (node (ref "R56") (pin "2") (pinfunction "2_2") (pintype "passive"))
    )
    (net (code "100") (name "Net-(R3-Pad2)") (class "Default")
      (node (ref "R3") (pin "2") (pinfunction "2_2") (pintype "passive"))
      (node (ref "VR1") (pin "2") (pinfunction "2_2") (pintype "passive"))
    )
    (net (code "101") (name "Net-(R9-Pad2)") (class "Default")
      (node (ref "R9") (pin "2") (pinfunction "2_2") (pintype "passive"))
      (node (ref "VR2") (pin "2") (pinfunction "2_2") (pintype "passive"))
    )
    (net (code "102") (name "Net-(R14-Pad2)") (class "Default")
      (node (ref "R14") (pin "2") (pinfunction "2_2") (pintype "passive"))
      (node (ref "VR3") (pin "2") (pinfunction "2_2") (pintype "passive"))
    )
    (net (code "103") (name "Net-(R20-Pad2)") (class "Default")
      (node (ref "R20") (pin "2") (pinfunction "2_2") (pintype "passive"))
      (node (ref "VR4") (pin "2") (pinfunction "2_2") (pintype "passive"))
    )
    (net (code "104") (name "Net-(R21-Pad2)") (class "Default")
      (node (ref "R21") (pin "2") (pinfunction "2_2") (pintype "passive"))
      (node (ref "VR5") (pin "2") (pinfunction "2_2") (pintype "passive"))
    )
    (net (code "105") (name "Net-(R26-Pad2)") (class "Default")
      (node (ref "R26") (pin "2") (pinfunction "2_2") (pintype "passive"))
      (node (ref "VR6") (pin "2") (pinfunction "2_2") (pintype "passive"))
    )
    (net (code "106") (name "Net-(R32-Pad2)") (class "Default")
      (node (ref "R32") (pin "2") (pinfunction "2_2") (pintype "passive"))
      (node (ref "VR7") (pin "2") (pinfunction "2_2") (pintype "passive"))
    )
    (net (code "107") (name "Net-(R39-Pad2)") (class "Default")
      (node (ref "R39") (pin "2") (pinfunction "2_2") (pintype "passive"))
      (node (ref "VR8") (pin "2") (pinfunction "2_2") (pintype "passive"))
    )
    (net (code "108") (name "Net-(R44-Pad2)") (class "Default")
      (node (ref "R44") (pin "2") (pinfunction "2_2") (pintype "passive"))
      (node (ref "VR9") (pin "2") (pinfunction "2_2") (pintype "passive"))
    )
    (net (code "109") (name "Net-(R69-Pad2)") (class "Default")
      (node (ref "R69") (pin "2") (pinfunction "2_2") (pintype "passive"))
      (node (ref "VR10") (pin "2") (pinfunction "2_2") (pintype "passive"))
    )
    (net (code "110") (name "Net-(R75-Pad2)") (class "Default")
      (node (ref "R75") (pin "2") (pinfunction "2_2") (pintype "passive"))
      (node (ref "VR11") (pin "2") (pinfunction "2_2") (pintype "passive"))
    )
    (net (code "111") (name "Net-(U2-PH0{slash}OSC_IN)") (class "Default")
      (node (ref "C47") (pin "2") (pinfunction "2_2") (pintype "passive"))
      (node (ref "U2") (pin "12") (pinfunction "PH0/OSC_IN_12") (pintype "bidirectional"))
      (node (ref "Y1") (pin "2") (pinfunction "2_2") (pintype "passive"))
    )
    (net (code "112") (name "Net-(U2-PH1{slash}OSC_OUT)") (class "Default")
      (node (ref "C46") (pin "2") (pinfunction "2_2") (pintype "passive"))
      (node (ref "U2") (pin "13") (pinfunction "PH1/OSC_OUT_13") (pintype "bidirectional"))
      (node (ref "Y1") (pin "1") (pinfunction "1_1") (pintype "passive"))
    )
    (net (code "113") (name "Net-(U3-XTI{slash}MCLK)") (class "Default")
      (node (ref "C18") (pin "2") (pinfunction "2_2") (pintype "passive"))
      (node (ref "U3") (pin "25") (pinfunction "XTI/MCLK_25") (pintype "bidirectional"))
      (node (ref "Y2") (pin "2") (pinfunction "2_2") (pintype "passive"))
    )
    (net (code "114") (name "Net-(U3-XTO)") (class "Default")
      (node (ref "C19") (pin "2") (pinfunction "2_2") (pintype "passive"))
      (node (ref "U3") (pin "26") (pinfunction "XTO_26") (pintype "bidirectional"))
      (node (ref "Y2") (pin "1") (pinfunction "1_1") (pintype "passive"))
    )
    (net (code "115") (name "Net-(U6A--IN)") (class "Default")
      (node (ref "R29") (pin "1") (pinfunction "1_1") (pintype "passive"))
      (node (ref "U6") (pin "2") (pinfunction "-IN_2") (pintype "input"))
      (node (ref "VR4") (pin "3") (pinfunction "3_3") (pintype "passive"))
    )
    (net (code "116") (name "Net-(U6A-OUT)") (class "Default")
      (node (ref "R29") (pin "2") (pinfunction "2_2") (pintype "passive"))
      (node (ref "R33") (pin "1") (pinfunction "1_1") (pintype "passive"))
      (node (ref "U6") (pin "1") (pinfunction "OUT_1") (pintype "output"))
    )
    (net (code "117") (name "Net-(U6B--IN)") (class "Default")
      (node (ref "R8") (pin "1") (pinfunction "1_1") (pintype "passive"))
      (node (ref "U6") (pin "6") (pinfunction "-IN_6") (pintype "input"))
      (node (ref "VR1") (pin "3") (pinfunction "3_3") (pintype "passive"))
    )
    (net (code "118") (name "Net-(U6B-OUT)") (class "Default")
      (node (ref "R7") (pin "1") (pinfunction "1_1") (pintype "passive"))
      (node (ref "R8") (pin "2") (pinfunction "2_2") (pintype "passive"))
      (node (ref "U6") (pin "7") (pinfunction "OUT_7") (pintype "output"))
    )
    (net (code "119") (name "Net-(U6C--IN)") (class "Default")
      (node (ref "R13") (pin "1") (pinfunction "1_1") (pintype "passive"))
      (node (ref "U6") (pin "9") (pinfunction "-IN_9") (pintype "input"))
      (node (ref "VR2") (pin "3") (pinfunction "3_3") (pintype "passive"))
    )
    (net (code "120") (name "Net-(U6C-OUT)") (class "Default")
      (node (ref "R12") (pin "1") (pinfunction "1_1") (pintype "passive"))
      (node (ref "R13") (pin "2") (pinfunction "2_2") (pintype "passive"))
      (node (ref "U6") (pin "8") (pinfunction "OUT_8") (pintype "output"))
    )
    (net (code "121") (name "Net-(U6D--IN)") (class "Default")
      (node (ref "R18") (pin "1") (pinfunction "1_1") (pintype "passive"))
      (node (ref "U6") (pin "13") (pinfunction "-IN_13") (pintype "input"))
      (node (ref "VR3") (pin "3") (pinfunction "3_3") (pintype "passive"))
    )
    (net (code "122") (name "Net-(U6D-OUT)") (class "Default")
      (node (ref "R17") (pin "1") (pinfunction "1_1") (pintype "passive"))
      (node (ref "R18") (pin "2") (pinfunction "2_2") (pintype "passive"))
      (node (ref "U6") (pin "14") (pinfunction "OUT_14") (pintype "output"))
    )
    (net (code "123") (name "Net-(U7A--IN)") (class "Default")
      (node (ref "R48") (pin "1") (pinfunction "1_1") (pintype "passive"))
      (node (ref "U7") (pin "2") (pinfunction "-IN_2") (pintype "input"))
      (node (ref "VR9") (pin "3") (pinfunction "3_3") (pintype "passive"))
    )
    (net (code "124") (name "Net-(U7A-OUT)") (class "Default")
      (node (ref "R47") (pin "1") (pinfunction "1_1") (pintype "passive"))
      (node (ref "R48") (pin "2") (pinfunction "2_2") (pintype "passive"))
      (node (ref "U7") (pin "1") (pinfunction "OUT_1") (pintype "output"))
    )
    (net (code "125") (name "Net-(U7B--IN)") (class "Default")
      (node (ref "R25") (pin "1") (pinfunction "1_1") (pintype "passive"))
      (node (ref "U7") (pin "6") (pinfunction "-IN_6") (pintype "input"))
      (node (ref "VR5") (pin "3") (pinfunction "3_3") (pintype "passive"))
    )
    (net (code "126") (name "Net-(U7B-OUT)") (class "Default")
      (node (ref "R24") (pin "1") (pinfunction "1_1") (pintype "passive"))
      (node (ref "R25") (pin "2") (pinfunction "2_2") (pintype "passive"))
      (node (ref "U7") (pin "7") (pinfunction "OUT_7") (pintype "output"))
    )
    (net (code "127") (name "Net-(U7C--IN)") (class "Default")
      (node (ref "R31") (pin "1") (pinfunction "1_1") (pintype "passive"))
      (node (ref "U7") (pin "9") (pinfunction "-IN_9") (pintype "input"))
      (node (ref "VR6") (pin "3") (pinfunction "3_3") (pintype "passive"))
    )
    (net (code "128") (name "Net-(U7C-OUT)") (class "Default")
      (node (ref "R30") (pin "1") (pinfunction "1_1") (pintype "passive"))
      (node (ref "R31") (pin "2") (pinfunction "2_2") (pintype "passive"))
      (node (ref "U7") (pin "8") (pinfunction "OUT_8") (pintype "output"))
    )
    (net (code "129") (name "Net-(U7D--IN)") (class "Default")
      (node (ref "R38") (pin "1") (pinfunction "1_1") (pintype "passive"))
      (node (ref "U7") (pin "13") (pinfunction "-IN_13") (pintype "input"))
      (node (ref "VR7") (pin "3") (pinfunction "3_3") (pintype "passive"))
    )
    (net (code "130") (name "Net-(U7D-OUT)") (class "Default")
      (node (ref "R36") (pin "1") (pinfunction "1_1") (pintype "passive"))
      (node (ref "R38") (pin "2") (pinfunction "2_2") (pintype "passive"))
      (node (ref "U7") (pin "14") (pinfunction "OUT_14") (pintype "output"))
    )
    (net (code "131") (name "Net-(U8A--IN)") (class "Default")
      (node (ref "R43") (pin "1") (pinfunction "1_1") (pintype "passive"))
      (node (ref "U8") (pin "2") (pinfunction "-IN_2") (pintype "input"))
      (node (ref "VR8") (pin "3") (pinfunction "3_3") (pintype "passive"))
    )
    (net (code "132") (name "Net-(U8A-OUT)") (class "Default")
      (node (ref "R42") (pin "1") (pinfunction "1_1") (pintype "passive"))
      (node (ref "R43") (pin "2") (pinfunction "2_2") (pintype "passive"))
      (node (ref "U8") (pin "1") (pinfunction "OUT_1") (pintype "output"))
    )
    (net (code "133") (name "Net-(U8B-+IN)") (class "Default")
      (node (ref "J2") (pin "TIP") (pinfunction "TIP_TIP") (pintype "passive"))
      (node (ref "R52") (pin "2") (pinfunction "2_2") (pintype "passive"))
      (node (ref "U8") (pin "5") (pinfunction "+IN_5") (pintype "input"))
    )
    (net (code "134") (name "Net-(U8B--IN)") (class "Default")
      (node (ref "R53") (pin "2") (pinfunction "2_2") (pintype "passive"))
      (node (ref "U8") (pin "6") (pinfunction "-IN_6") (pintype "input"))
      (node (ref "U8") (pin "7") (pinfunction "OUT_7") (pintype "output"))
    )
    (net (code "135") (name "Net-(U9A--IN)") (class "Default")
      (node (ref "C34") (pin "1") (pinfunction "1_1") (pintype "passive"))
      (node (ref "R19") (pin "2") (pinfunction "2_2") (pintype "passive"))
      (node (ref "R33") (pin "2") (pinfunction "2_2") (pintype "passive"))
      (node (ref "R37") (pin "1") (pinfunction "1_1") (pintype "passive"))
      (node (ref "U9") (pin "2") (pinfunction "-IN_2") (pintype "input"))
      (node (ref "VR4") (pin "1") (pinfunction "1_1") (pintype "passive"))
    )
    (net (code "136") (name "Net-(U9B--IN)") (class "Default")
      (node (ref "C15") (pin "1") (pinfunction "1_1") (pintype "passive"))
      (node (ref "R5") (pin "2") (pinfunction "2_2") (pintype "passive"))
      (node (ref "R6") (pin "1") (pinfunction "1_1") (pintype "passive"))
      (node (ref "R7") (pin "2") (pinfunction "2_2") (pintype "passive"))
      (node (ref "U9") (pin "6") (pinfunction "-IN_6") (pintype "input"))
      (node (ref "VR1") (pin "1") (pinfunction "1_1") (pintype "passive"))
    )
    (net (code "137") (name "Net-(U9C--IN)") (class "Default")
      (node (ref "C16") (pin "1") (pinfunction "1_1") (pintype "passive"))
      (node (ref "R10") (pin "2") (pinfunction "2_2") (pintype "passive"))
      (node (ref "R11") (pin "1") (pinfunction "1_1") (pintype "passive"))
      (node (ref "R12") (pin "2") (pinfunction "2_2") (pintype "passive"))
      (node (ref "U9") (pin "9") (pinfunction "-IN_9") (pintype "input"))
      (node (ref "VR2") (pin "1") (pinfunction "1_1") (pintype "passive"))
    )
    (net (code "138") (name "Net-(U9D--IN)") (class "Default")
      (node (ref "C17") (pin "1") (pinfunction "1_1") (pintype "passive"))
      (node (ref "R15") (pin "2") (pinfunction "2_2") (pintype "passive"))
      (node (ref "R16") (pin "1") (pinfunction "1_1") (pintype "passive"))
      (node (ref "R17") (pin "2") (pinfunction "2_2") (pintype "passive"))
      (node (ref "U9") (pin "13") (pinfunction "-IN_13") (pintype "input"))
      (node (ref "VR3") (pin "1") (pinfunction "1_1") (pintype "passive"))
    )
    (net (code "139") (name "Net-(U10A--IN)") (class "Default")
      (node (ref "C25") (pin "1") (pinfunction "1_1") (pintype "passive"))
      (node (ref "R45") (pin "2") (pinfunction "2_2") (pintype "passive"))
      (node (ref "R46") (pin "1") (pinfunction "1_1") (pintype "passive"))
      (node (ref "R47") (pin "2") (pinfunction "2_2") (pintype "passive"))
      (node (ref "U10") (pin "2") (pinfunction "-IN_2") (pintype "input"))
      (node (ref "VR9") (pin "1") (pinfunction "1_1") (pintype "passive"))
    )
    (net (code "140") (name "Net-(U10B--IN)") (class "Default")
      (node (ref "C20") (pin "1") (pinfunction "1_1") (pintype "passive"))
      (node (ref "R22") (pin "2") (pinfunction "2_2") (pintype "passive"))
      (node (ref "R23") (pin "1") (pinfunction "1_1") (pintype "passive"))
      (node (ref "R24") (pin "2") (pinfunction "2_2") (pintype "passive"))
      (node (ref "U10") (pin "6") (pinfunction "-IN_6") (pintype "input"))
      (node (ref "VR5") (pin "1") (pinfunction "1_1") (pintype "passive"))
    )
    (net (code "141") (name "Net-(U10C--IN)") (class "Default")
      (node (ref "C21") (pin "1") (pinfunction "1_1") (pintype "passive"))
      (node (ref "R27") (pin "2") (pinfunction "2_2") (pintype "passive"))
      (node (ref "R28") (pin "1") (pinfunction "1_1") (pintype "passive"))
      (node (ref "R30") (pin "2") (pinfunction "2_2") (pintype "passive"))
      (node (ref "U10") (pin "9") (pinfunction "-IN_9") (pintype "input"))
      (node (ref "VR6") (pin "1") (pinfunction "1_1") (pintype "passive"))
    )
    (net (code "142") (name "Net-(U10D--IN)") (class "Default")
      (node (ref "C23") (pin "1") (pinfunction "1_1") (pintype "passive"))
      (node (ref "R34") (pin "2") (pinfunction "2_2") (pintype "passive"))
      (node (ref "R35") (pin "1") (pinfunction "1_1") (pintype "passive"))
      (node (ref "R36") (pin "2") (pinfunction "2_2") (pintype "passive"))
      (node (ref "U10") (pin "13") (pinfunction "-IN_13") (pintype "input"))
      (node (ref "VR7") (pin "1") (pinfunction "1_1") (pintype "passive"))
    )
    (net (code "143") (name "Net-(U11A--IN)") (class "Default")
      (node (ref "C24") (pin "1") (pinfunction "1_1") (pintype "passive"))
      (node (ref "R40") (pin "2") (pinfunction "2_2") (pintype "passive"))
      (node (ref "R41") (pin "1") (pinfunction "1_1") (pintype "passive"))
      (node (ref "R42") (pin "2") (pinfunction "2_2") (pintype "passive"))
      (node (ref "U11") (pin "2") (pinfunction "-IN_2") (pintype "input"))
      (node (ref "VR8") (pin "1") (pinfunction "1_1") (pintype "passive"))
    )
    (net (code "144") (name "Net-(U11B--IN)") (class "Default")
      (node (ref "C26") (pin "1") (pinfunction "1_1") (pintype "passive"))
      (node (ref "R49") (pin "2") (pinfunction "2_2") (pintype "passive"))
      (node (ref "R50") (pin "2") (pinfunction "2_2") (pintype "passive"))
      (node (ref "R51") (pin "1") (pinfunction "1_1") (pintype "passive"))
      (node (ref "U11") (pin "6") (pinfunction "-IN_6") (pintype "input"))
    )
    (net (code "145") (name "Net-(U11C--IN)") (class "Default")
      (node (ref "U11") (pin "8") (pinfunction "OUT_8") (pintype "output"))
      (node (ref "U11") (pin "9") (pinfunction "-IN_9") (pintype "input"))
    )
    (net (code "146") (name "Net-(U11D--IN)") (class "Default")
      (node (ref "U11") (pin "13") (pinfunction "-IN_13") (pintype "input"))
      (node (ref "U11") (pin "14") (pinfunction "OUT_14") (pintype "output"))
    )
    (net (code "147") (name "Net-(U12A--IN)") (class "Default")
      (node (ref "C31") (pin "1") (pinfunction "1_1") (pintype "passive"))
      (node (ref "R62") (pin "2") (pinfunction "2_2") (pintype "passive"))
      (node (ref "U12") (pin "2") (pinfunction "-IN_2") (pintype "input"))
      (node (ref "U18") (pin "5") (pinfunction "OUT_5") (pintype "output"))
    )
    (net (code "148") (name "Net-(U12A-OUT)") (class "Default")
      (node (ref "C31") (pin "2") (pinfunction "2_2") (pintype "passive"))
      (node (ref "R62") (pin "1") (pinfunction "1_1") (pintype "passive"))
      (node (ref "R65") (pin "2") (pinfunction "2_2") (pintype "passive"))
      (node (ref "U12") (pin "1") (pinfunction "OUT_1") (pintype "output"))
    )
    (net (code "149") (name "Net-(U12B--IN)") (class "Default")
      (node (ref "C32") (pin "1") (pinfunction "1_1") (pintype "passive"))
      (node (ref "R67") (pin "2") (pinfunction "2_2") (pintype "passive"))
      (node (ref "U12") (pin "6") (pinfunction "-IN_6") (pintype "input"))
      (node (ref "U18") (pin "12") (pinfunction "OUT_12") (pintype "output"))
    )
    (net (code "150") (name "Net-(U12B-OUT)") (class "Default")
      (node (ref "C32") (pin "2") (pinfunction "2_2") (pintype "passive"))
      (node (ref "R67") (pin "1") (pinfunction "1_1") (pintype "passive"))
      (node (ref "R68") (pin "2") (pinfunction "2_2") (pintype "passive"))
      (node (ref "U12") (pin "7") (pinfunction "OUT_7") (pintype "output"))
    )
    (net (code "151") (name "Net-(U12C--IN)") (class "Default")
      (node (ref "C38") (pin "1") (pinfunction "1_1") (pintype "passive"))
      (node (ref "R77") (pin "2") (pinfunction "2_2") (pintype "passive"))
      (node (ref "U12") (pin "9") (pinfunction "-IN_9") (pintype "input"))
      (node (ref "U13") (pin "12") (pinfunction "OUT_12") (pintype "output"))
    )
    (net (code "152") (name "Net-(U12C-OUT)") (class "Default")
      (node (ref "C38") (pin "2") (pinfunction "2_2") (pintype "passive"))
      (node (ref "R77") (pin "1") (pinfunction "1_1") (pintype "passive"))
      (node (ref "U12") (pin "8") (pinfunction "OUT_8") (pintype "output"))
      (node (ref "U19") (pin "3") (pinfunction "+IN_3") (pintype "input"))
    )
    (net (code "153") (name "Net-(U12D--IN)") (class "Default")
      (node (ref "C39") (pin "1") (pinfunction "1_1") (pintype "passive"))
      (node (ref "R79") (pin "2") (pinfunction "2_2") (pintype "passive"))
      (node (ref "U12") (pin "13") (pinfunction "-IN_13") (pintype "input"))
      (node (ref "U13") (pin "4") (pinfunction "OUT_4") (pintype "output"))
    )
    (net (code "154") (name "Net-(U12D-OUT)") (class "Default")
      (node (ref "C39") (pin "2") (pinfunction "2_2") (pintype "passive"))
      (node (ref "R79") (pin "1") (pinfunction "1_1") (pintype "passive"))
      (node (ref "U12") (pin "14") (pinfunction "OUT_14") (pintype "output"))
      (node (ref "U19") (pin "5") (pinfunction "+IN_5") (pintype "input"))
    )
    (net (code "155") (name "Net-(U13A-IN)") (class "Default")
      (node (ref "R84") (pin "1") (pinfunction "1_1") (pintype "passive"))
      (node (ref "R85") (pin "2") (pinfunction "2_2") (pintype "passive"))
      (node (ref "U13") (pin "2") (pinfunction "IN_2") (pintype "input"))
    )
    (net (code "156") (name "Net-(U13B-IN)") (class "Default")
      (node (ref "R109") (pin "2") (pinfunction "2_2") (pintype "passive"))
      (node (ref "U13") (pin "7") (pinfunction "IN_7") (pintype "input"))
    )
    (net (code "157") (name "Net-(U13C-IN)") (class "Default")
      (node (ref "R80") (pin "1") (pinfunction "1_1") (pintype "passive"))
      (node (ref "R81") (pin "2") (pinfunction "2_2") (pintype "passive"))
      (node (ref "U13") (pin "10") (pinfunction "IN_10") (pintype "input"))
    )
    (net (code "158") (name "Net-(U13D-IN)") (class "Default")
      (node (ref "R110") (pin "2") (pinfunction "2_2") (pintype "passive"))
      (node (ref "U13") (pin "15") (pinfunction "IN_15") (pintype "input"))
    )
    (net (code "159") (name "Net-(U16A--IN)") (class "Default")
      (node (ref "R111") (pin "2") (pinfunction "2_2") (pintype "passive"))
      (node (ref "R112") (pin "1") (pinfunction "1_1") (pintype "passive"))
      (node (ref "U16") (pin "2") (pinfunction "-IN_2") (pintype "input"))
    )
    (net (code "160") (name "Net-(U16B--IN)") (class "Default")
      (node (ref "U16") (pin "6") (pinfunction "-IN_6") (pintype "input"))
      (node (ref "U16") (pin "7") (pinfunction "OUT_7") (pintype "output"))
    )
    (net (code "161") (name "Net-(U18A-CTRL)") (class "Default")
      (node (ref "C30") (pin "2") (pinfunction "2_2") (pintype "passive"))
      (node (ref "U18") (pin "11") (pinfunction "CTRL_11") (pintype "input"))
      (node (ref "U18") (pin "3") (pinfunction "CTRL_3") (pintype "input"))
      (node (ref "U18") (pin "6") (pinfunction "CTRL_6") (pintype "input"))
      (node (ref "U8") (pin "14") (pinfunction "OUT_14") (pintype "output"))
    )
    (net (code "162") (name "Net-(U18A-IN)") (class "Default")
      (node (ref "R63") (pin "2") (pinfunction "2_2") (pintype "passive"))
      (node (ref "R66") (pin "1") (pinfunction "1_1") (pintype "passive"))
      (node (ref "U18") (pin "2") (pinfunction "IN_2") (pintype "input"))
    )
    (net (code "163") (name "Net-(U18A-OUT)") (class "Default")
      (node (ref "C30") (pin "1") (pinfunction "1_1") (pintype "passive"))
      (node (ref "R64") (pin "1") (pinfunction "1_1") (pintype "passive"))
      (node (ref "R69") (pin "1") (pinfunction "1_1") (pintype "passive"))
      (node (ref "R70") (pin "1") (pinfunction "1_1") (pintype "passive"))
      (node (ref "U18") (pin "4") (pinfunction "OUT_4") (pintype "output"))
      (node (ref "U8") (pin "13") (pinfunction "-IN_13") (pintype "input"))
    )
    (net (code "164") (name "Net-(U18B-IN)") (class "Default")
      (node (ref "R59") (pin "2") (pinfunction "2_2") (pintype "passive"))
      (node (ref "R61") (pin "1") (pinfunction "1_1") (pintype "passive"))
      (node (ref "U18") (pin "7") (pinfunction "IN_7") (pintype "input"))
    )
    (net (code "165") (name "Net-(U18C-IN)") (class "Default")
      (node (ref "R58") (pin "2") (pinfunction "2_2") (pintype "passive"))
      (node (ref "R60") (pin "1") (pinfunction "1_1") (pintype "passive"))
      (node (ref "U18") (pin "10") (pinfunction "IN_10") (pintype "input"))
    )
    (net (code "166") (name "Net-(U18D-IN)") (class "Default")
      (node (ref "R72") (pin "2") (pinfunction "2_2") (pintype "passive"))
      (node (ref "R74") (pin "1") (pinfunction "1_1") (pintype "passive"))
      (node (ref "U18") (pin "15") (pinfunction "IN_15") (pintype "input"))
    )
    (net (code "167") (name "Net-(U18D-OUT)") (class "Default")
      (node (ref "C37") (pin "1") (pinfunction "1_1") (pintype "passive"))
      (node (ref "R73") (pin "1") (pinfunction "1_1") (pintype "passive"))
      (node (ref "R75") (pin "1") (pinfunction "1_1") (pintype "passive"))
      (node (ref "R76") (pin "1") (pinfunction "1_1") (pintype "passive"))
      (node (ref "U18") (pin "13") (pinfunction "OUT_13") (pintype "output"))
      (node (ref "U8") (pin "9") (pinfunction "-IN_9") (pintype "input"))
    )
    (net (code "168") (name "Net-(U19A--IN)") (class "Default")
      (node (ref "R113") (pin "1") (pinfunction "1_1") (pintype "passive"))
      (node (ref "R114") (pin "1") (pinfunction "1_1") (pintype "passive"))
      (node (ref "U19") (pin "2") (pinfunction "-IN_2") (pintype "input"))
    )
    (net (code "169") (name "Net-(U19A-OUT)") (class "Default")
      (node (ref "R114") (pin "2") (pinfunction "2_2") (pintype "passive"))
      (node (ref "R78") (pin "2") (pinfunction "2_2") (pintype "passive"))
      (node (ref "U19") (pin "1") (pinfunction "OUT_1") (pintype "output"))
    )
    (net (code "170") (name "Net-(U19B--IN)") (class "Default")
      (node (ref "R115") (pin "1") (pinfunction "1_1") (pintype "passive"))
      (node (ref "R116") (pin "1") (pinfunction "1_1") (pintype "passive"))
      (node (ref "U19") (pin "6") (pinfunction "-IN_6") (pintype "input"))
    )
    (net (code "171") (name "Net-(U19B-OUT)") (class "Default")
      (node (ref "R116") (pin "2") (pinfunction "2_2") (pintype "passive"))
      (node (ref "R83") (pin "2") (pinfunction "2_2") (pintype "passive"))
      (node (ref "U19") (pin "7") (pinfunction "OUT_7") (pintype "output"))
    )
    (net (code "172") (name "PITCH_CV") (class "Default")
      (node (ref "C16") (pin "2") (pinfunction "2_2") (pintype "passive"))
      (node (ref "R11") (pin "2") (pinfunction "2_2") (pintype "passive"))
      (node (ref "U2") (pin "25") (pinfunction "PA2_25") (pintype "bidirectional"))
      (node (ref "U9") (pin "8") (pinfunction "OUT_8") (pintype "output"))
    )
    (net (code "173") (name "PITCH_POT") (class "Default")
      (node (ref "U17") (pin "2") (pinfunction "X6_2") (pintype "bidirectional"))
      (node (ref "VR15") (pin "2") (pinfunction "2_2") (pintype "passive"))
    )
    (net (code "174") (name "POSITION_CV") (class "Default")
      (node (ref "C34") (pin "2") (pinfunction "2_2") (pintype "passive"))
      (node (ref "R37") (pin "2") (pinfunction "2_2") (pintype "passive"))
      (node (ref "U2") (pin "23") (pinfunction "PA0/WKUP_23") (pintype "bidirectional"))
      (node (ref "U9") (pin "1") (pinfunction "OUT_1") (pintype "output"))
    )
    (net (code "175") (name "POSITION_POT") (class "Default")
      (node (ref "U17") (pin "1") (pinfunction "X4_1") (pintype "bidirectional"))
      (node (ref "VR14") (pin "2") (pinfunction "2_2") (pintype "passive"))
    )
    (net (code "176") (name "RESET") (class "Default")
      (node (ref "P2") (pin "10") (pinfunction "10_10") (pintype "passive"))
      (node (ref "R106") (pin "1") (pinfunction "1_1") (pintype "passive"))
      (node (ref "SW5") (pin "B") (pinfunction "S_B") (pintype "passive"))
      (node (ref "SW5") (pin "B'") (pinfunction "S1_B'") (pintype "passive"))
      (node (ref "U2") (pin "14") (pinfunction "NRST_14") (pintype "bidirectional"))
    )
    (net (code "177") (name "RIN") (class "Default")
      (node (ref "C45") (pin "P$1") (pinfunction "POS_P$1") (pintype "passive"))
      (node (ref "U3") (pin "19") (pinfunction "RLINEIN_19") (pintype "bidirectional"))
    )
    (net (code "178") (name "ROUT") (class "Default")
      (node (ref "C43") (pin "P$1") (pinfunction "POS_P$1") (pintype "passive"))
      (node (ref "U3") (pin "13") (pinfunction "ROUT_13") (pintype "bidirectional"))
    )
    (net (code "179") (name "RX") (class "Default")
      (node (ref "JP1") (pin "4") (pinfunction "4_4") (pintype "passive"))
      (node (ref "U2") (pin "69") (pinfunction "PA10_69") (pintype "bidirectional"))
    )
    (net (code "180") (name "SHAPE_CV") (class "Default")
      (node (ref "C25") (pin "2") (pinfunction "2_2") (pintype "passive"))
      (node (ref "R46") (pin "2") (pinfunction "2_2") (pintype "passive"))
      (node (ref "U10") (pin "1") (pinfunction "OUT_1") (pintype "output"))
      (node (ref "U2") (pin "30") (pinfunction "PA5_30") (pintype "bidirectional"))
    )
    (net (code "181") (name "SHAPE_POT") (class "Default")
      (node (ref "U17") (pin "5") (pinfunction "X5_5") (pintype "bidirectional"))
      (node (ref "VR18") (pin "2") (pinfunction "2_2") (pintype "passive"))
    )
    (net (code "182") (name "SIZE_CV") (class "Default")
      (node (ref "C15") (pin "2") (pinfunction "2_2") (pintype "passive"))
      (node (ref "R6") (pin "2") (pinfunction "2_2") (pintype "passive"))
      (node (ref "U2") (pin "24") (pinfunction "PA1_24") (pintype "bidirectional"))
      (node (ref "U9") (pin "7") (pinfunction "OUT_7") (pintype "output"))
    )
    (net (code "183") (name "SIZE_POT") (class "Default")
      (node (ref "U2") (pin "16") (pinfunction "PC1_16") (pintype "bidirectional"))
      (node (ref "VR20") (pin "2") (pinfunction "2_2") (pintype "passive"))
    )
    (net (code "184") (name "SPACE_CV") (class "Default")
      (node (ref "C24") (pin "2") (pinfunction "2_2") (pintype "passive"))
      (node (ref "R41") (pin "2") (pinfunction "2_2") (pintype "passive"))
      (node (ref "U11") (pin "1") (pinfunction "OUT_1") (pintype "output"))
      (node (ref "U2") (pin "17") (pinfunction "PC2_17") (pintype "bidirectional"))
    )
    (net (code "185") (name "SPACE_POT") (class "Default")
      (node (ref "U17") (pin "15") (pinfunction "X2_15") (pintype "bidirectional"))
      (node (ref "VR13") (pin "2") (pinfunction "2_2") (pintype "passive"))
    )
    (net (code "186") (name "SW_BANK") (class "Default")
      (node (ref "S9") (pin "1") (pinfunction "1_1") (pintype "passive"))
      (node (ref "U2") (pin "43") (pinfunction "PE12_43") (pintype "bidirectional"))
    )
    (net (code "187") (name "SW_HOLD") (class "Default")
      (node (ref "S3") (pin "1") (pinfunction "1_1") (pintype "passive"))
      (node (ref "U2") (pin "41") (pinfunction "PE10_41") (pintype "bidirectional"))
    )
    (net (code "188") (name "SW_MUTE_INS") (class "Default")
      (node (ref "S2") (pin "3") (pinfunction "3_3") (pintype "passive"))
      (node (ref "U2") (pin "38") (pinfunction "PE7_38") (pintype "bidirectional"))
    )
    (net (code "189") (name "SW_MUTE_OUTS") (class "Default")
      (node (ref "S1") (pin "3") (pinfunction "3_3") (pintype "passive"))
      (node (ref "U2") (pin "39") (pinfunction "PE8_39") (pintype "bidirectional"))
    )
    (net (code "190") (name "SW_TIME") (class "Default")
      (node (ref "S7") (pin "1") (pinfunction "1_1") (pintype "passive"))
      (node (ref "U2") (pin "42") (pinfunction "PE11_42") (pintype "bidirectional"))
    )
    (net (code "191") (name "SW_TRIG") (class "Default")
      (node (ref "S8") (pin "1") (pinfunction "1_1") (pintype "passive"))
      (node (ref "U2") (pin "40") (pinfunction "PE9_40") (pintype "bidirectional"))
    )
    (net (code "192") (name "TX") (class "Default")
      (node (ref "JP1") (pin "5") (pinfunction "5_5") (pintype "passive"))
      (node (ref "U2") (pin "68") (pinfunction "PA9_68") (pintype "bidirectional"))
    )
    (net (code "193") (name "VBAT") (class "Default")
      (node (ref "U2") (pin "6") (pinfunction "VBAT_6") (pintype "power_in"))
    )
    (net (code "194") (name "VCAP_1") (class "Default")
      (node (ref "C48") (pin "2") (pinfunction "2_2") (pintype "passive"))
      (node (ref "U2") (pin "49") (pinfunction "VCAP_1_49") (pintype "power_in"))
    )
    (net (code "195") (name "VCAP_2") (class "Default")
      (node (ref "C49") (pin "2") (pinfunction "2_2") (pintype "passive"))
      (node (ref "U2") (pin "73") (pinfunction "VCAP_2_73") (pintype "power_in"))
    )
    (net (code "196") (name "VOCT_CV") (class "Default")
      (node (ref "C26") (pin "2") (pinfunction "2_2") (pintype "passive"))
      (node (ref "R51") (pin "2") (pinfunction "2_2") (pintype "passive"))
      (node (ref "U11") (pin "7") (pinfunction "OUT_7") (pintype "output"))
      (node (ref "U2") (pin "15") (pinfunction "PC0_15") (pintype "bidirectional"))
    )
    (net (code "197") (name "VU_METER_IN_1") (class "Default")
      (node (ref "R88") (pin "2") (pinfunction "2_2") (pintype "passive"))
      (node (ref "U2") (pin "59") (pinfunction "PD12_59") (pintype "bidirectional"))
    )
    (net (code "198") (name "VU_METER_IN_2") (class "Default")
      (node (ref "R89") (pin "2") (pinfunction "2_2") (pintype "passive"))
      (node (ref "U2") (pin "60") (pinfunction "PD13_60") (pintype "bidirectional"))
    )
    (net (code "199") (name "VU_METER_IN_3") (class "Default")
      (node (ref "R90") (pin "2") (pinfunction "2_2") (pintype "passive"))
      (node (ref "U2") (pin "61") (pinfunction "PD14_61") (pintype "bidirectional"))
    )
    (net (code "200") (name "VU_METER_IN_4") (class "Default")
      (node (ref "R91") (pin "2") (pinfunction "2_2") (pintype "passive"))
      (node (ref "U2") (pin "62") (pinfunction "PD15_62") (pintype "bidirectional"))
    )
    (net (code "201") (name "VU_METER_OUT_1") (class "Default")
      (node (ref "R92") (pin "2") (pinfunction "2_2") (pintype "passive"))
      (node (ref "U2") (pin "66") (pinfunction "PC9_66") (pintype "bidirectional"))
    )
    (net (code "202") (name "VU_METER_OUT_2") (class "Default")
      (node (ref "R93") (pin "2") (pinfunction "2_2") (pintype "passive"))
      (node (ref "U2") (pin "65") (pinfunction "PC8_65") (pintype "bidirectional"))
    )
    (net (code "203") (name "VU_METER_OUT_3") (class "Default")
      (node (ref "R94") (pin "2") (pinfunction "2_2") (pintype "passive"))
      (node (ref "U2") (pin "64") (pinfunction "PC7_64") (pintype "bidirectional"))
    )
    (net (code "204") (name "VU_METER_OUT_4") (class "Default")
      (node (ref "R95") (pin "2") (pinfunction "2_2") (pintype "passive"))
      (node (ref "U2") (pin "63") (pinfunction "PC6_63") (pintype "bidirectional"))
    )
    (net (code "205") (name "WIDTH_CV") (class "Default")
      (node (ref "C21") (pin "2") (pinfunction "2_2") (pintype "passive"))
      (node (ref "R28") (pin "2") (pinfunction "2_2") (pintype "passive"))
      (node (ref "U10") (pin "8") (pinfunction "OUT_8") (pintype "output"))
      (node (ref "U2") (pin "32") (pinfunction "PA7_32") (pintype "bidirectional"))
    )
    (net (code "206") (name "WIDTH_POT") (class "Default")
      (node (ref "U17") (pin "13") (pinfunction "X0_13") (pintype "bidirectional"))
      (node (ref "VR12") (pin "2") (pinfunction "2_2") (pintype "passive"))
    )
    (net (code "207") (name "unconnected-(J11-PadNORM)") (class "Default")
      (node (ref "J11") (pin "NORM") (pinfunction "NORM_NORM") (pintype "passive"))
    )
    (net (code "208") (name "unconnected-(J14-PadNORM)") (class "Default")
      (node (ref "J14") (pin "NORM") (pinfunction "NORM_NORM") (pintype "passive"))
    )
    (net (code "209") (name "unconnected-(J16-PadNORM)") (class "Default")
      (node (ref "J16") (pin "NORM") (pinfunction "NORM_NORM") (pintype "passive"))
    )
    (net (code "210") (name "unconnected-(J17-PadNORM)") (class "Default")
      (node (ref "J17") (pin "NORM") (pinfunction "NORM_NORM") (pintype "passive"))
    )
    (net (code "211") (name "unconnected-(J18-PadNORM)") (class "Default")
      (node (ref "J18") (pin "NORM") (pinfunction "NORM_NORM") (pintype "passive"))
    )
    (net (code "212") (name "unconnected-(J19-PadNORM)") (class "Default")
      (node (ref "J19") (pin "NORM") (pinfunction "NORM_NORM") (pintype "passive"))
    )
    (net (code "213") (name "unconnected-(JP1-Pad2)") (class "Default")
      (node (ref "JP1") (pin "2") (pinfunction "2_2") (pintype "passive"))
    )
    (net (code "214") (name "unconnected-(JP1-Pad3)") (class "Default")
      (node (ref "JP1") (pin "3") (pinfunction "3_3") (pintype "passive"))
    )
    (net (code "215") (name "unconnected-(JP1-Pad6)") (class "Default")
      (node (ref "JP1") (pin "6") (pinfunction "6_6") (pintype "passive"))
    )
    (net (code "216") (name "unconnected-(P2-Pad7)") (class "Default")
      (node (ref "P2") (pin "7") (pinfunction "7_7") (pintype "passive"))
    )
    (net (code "217") (name "unconnected-(S1-Pad2)") (class "Default")
      (node (ref "S1") (pin "2") (pinfunction "2_2") (pintype "passive"))
    )
    (net (code "218") (name "unconnected-(S1-Pad4)") (class "Default")
      (node (ref "S1") (pin "4") (pinfunction "4_4") (pintype "passive"))
    )
    (net (code "219") (name "unconnected-(S2-Pad2)") (class "Default")
      (node (ref "S2") (pin "2") (pinfunction "2_2") (pintype "passive"))
    )
    (net (code "220") (name "unconnected-(S2-Pad4)") (class "Default")
      (node (ref "S2") (pin "4") (pinfunction "4_4") (pintype "passive"))
    )
    (net (code "221") (name "unconnected-(S3-Pad2)") (class "Default")
      (node (ref "S3") (pin "2") (pinfunction "2_2") (pintype "passive"))
    )
    (net (code "222") (name "unconnected-(S3-Pad4)") (class "Default")
      (node (ref "S3") (pin "4") (pinfunction "4_4") (pintype "passive"))
    )
    (net (code "223") (name "unconnected-(S7-Pad2)") (class "Default")
      (node (ref "S7") (pin "2") (pinfunction "2_2") (pintype "passive"))
    )
    (net (code "224") (name "unconnected-(S7-Pad4)") (class "Default")
      (node (ref "S7") (pin "4") (pinfunction "4_4") (pintype "passive"))
    )
    (net (code "225") (name "unconnected-(S8-Pad2)") (class "Default")
      (node (ref "S8") (pin "2") (pinfunction "2_2") (pintype "passive"))
    )
    (net (code "226") (name "unconnected-(S8-Pad4)") (class "Default")
      (node (ref "S8") (pin "4") (pinfunction "4_4") (pintype "passive"))
    )
    (net (code "227") (name "unconnected-(S9-Pad2)") (class "Default")
      (node (ref "S9") (pin "2") (pinfunction "2_2") (pintype "passive"))
    )
    (net (code "228") (name "unconnected-(S9-Pad4)") (class "Default")
      (node (ref "S9") (pin "4") (pinfunction "4_4") (pintype "passive"))
    )
    (net (code "229") (name "unconnected-(U2-PA8-Pad67)") (class "Default")
      (node (ref "U2") (pin "67") (pinfunction "PA8_67") (pintype "bidirectional"))
    )
    (net (code "230") (name "unconnected-(U2-PA11-Pad70)") (class "Default")
      (node (ref "U2") (pin "70") (pinfunction "PA11_70") (pintype "bidirectional"))
    )
    (net (code "231") (name "unconnected-(U2-PA12-Pad71)") (class "Default")
      (node (ref "U2") (pin "71") (pinfunction "PA12_71") (pintype "bidirectional"))
    )
    (net (code "232") (name "unconnected-(U2-PB2{slash}BOOT1-Pad37)") (class "Default")
      (node (ref "U2") (pin "37") (pinfunction "PB2/BOOT1_37") (pintype "bidirectional"))
    )
    (net (code "233") (name "unconnected-(U2-PB4-Pad90)") (class "Default")
      (node (ref "U2") (pin "90") (pinfunction "PB4_90") (pintype "bidirectional"))
    )
    (net (code "234") (name "unconnected-(U2-PB5-Pad91)") (class "Default")
      (node (ref "U2") (pin "91") (pinfunction "PB5_91") (pintype "bidirectional"))
    )
    (net (code "235") (name "unconnected-(U2-PB6-Pad92)") (class "Default")
      (node (ref "U2") (pin "92") (pinfunction "PB6_92") (pintype "bidirectional"))
    )
    (net (code "236") (name "unconnected-(U2-PB7-Pad93)") (class "Default")
      (node (ref "U2") (pin "93") (pinfunction "PB7_93") (pintype "bidirectional"))
    )
    (net (code "237") (name "unconnected-(U2-PB8-Pad95)") (class "Default")
      (node (ref "U2") (pin "95") (pinfunction "PB8_95") (pintype "bidirectional"))
    )
    (net (code "238") (name "unconnected-(U2-PB9-Pad96)") (class "Default")
      (node (ref "U2") (pin "96") (pinfunction "PB9_96") (pintype "bidirectional"))
    )
    (net (code "239") (name "unconnected-(U2-PC3-Pad18)") (class "Default")
      (node (ref "U2") (pin "18") (pinfunction "PC3_18") (pintype "bidirectional"))
    )
    (net (code "240") (name "unconnected-(U2-PC5-Pad34)") (class "Default")
      (node (ref "U2") (pin "34") (pinfunction "PC5_34") (pintype "bidirectional"))
    )
    (net (code "241") (name "unconnected-(U2-PC10-Pad78)") (class "Default")
      (node (ref "U2") (pin "78") (pinfunction "PC10_78") (pintype "bidirectional"))
    )
    (net (code "242") (name "unconnected-(U2-PC11-Pad79)") (class "Default")
      (node (ref "U2") (pin "79") (pinfunction "PC11_79") (pintype "bidirectional"))
    )
    (net (code "243") (name "unconnected-(U2-PC12-Pad80)") (class "Default")
      (node (ref "U2") (pin "80") (pinfunction "PC12_80") (pintype "bidirectional"))
    )
    (net (code "244") (name "unconnected-(U2-PC13-Pad7)") (class "Default")
      (node (ref "U2") (pin "7") (pinfunction "PC13_7") (pintype "bidirectional"))
    )
    (net (code "245") (name "unconnected-(U2-PC14{slash}OSC32_IN-Pad8)") (class "Default")
      (node (ref "U2") (pin "8") (pinfunction "PC14/OSC32_IN_8") (pintype "bidirectional"))
    )
    (net (code "246") (name "unconnected-(U2-PC15{slash}OSC32_OUT-Pad9)") (class "Default")
      (node (ref "U2") (pin "9") (pinfunction "PC15/OSC32_OUT_9") (pintype "bidirectional"))
    )
    (net (code "247") (name "unconnected-(U2-PD8-Pad55)") (class "Default")
      (node (ref "U2") (pin "55") (pinfunction "PD8_55") (pintype "bidirectional"))
    )
    (net (code "248") (name "unconnected-(U2-PD9-Pad56)") (class "Default")
      (node (ref "U2") (pin "56") (pinfunction "PD9_56") (pintype "bidirectional"))
    )
    (net (code "249") (name "unconnected-(U2-PD11-Pad58)") (class "Default")
      (node (ref "U2") (pin "58") (pinfunction "PD11_58") (pintype "bidirectional"))
    )
    (net (code "250") (name "unconnected-(U2-PE0-Pad97)") (class "Default")
      (node (ref "U2") (pin "97") (pinfunction "PE0_97") (pintype "bidirectional"))
    )
    (net (code "251") (name "unconnected-(U2-PE1-Pad98)") (class "Default")
      (node (ref "U2") (pin "98") (pinfunction "PE1_98") (pintype "bidirectional"))
    )
    (net (code "252") (name "unconnected-(U2-PE6-Pad5)") (class "Default")
      (node (ref "U2") (pin "5") (pinfunction "PE6_5") (pintype "bidirectional"))
    )
    (net (code "253") (name "unconnected-(U2-PE15-Pad46)") (class "Default")
      (node (ref "U2") (pin "46") (pinfunction "PE15_46") (pintype "bidirectional"))
    )
    (net (code "254") (name "unconnected-(U3-CLKOUT-Pad2)") (class "Default")
      (node (ref "U3") (pin "2") (pinfunction "CLKOUT_2") (pintype "bidirectional"))
    )
    (net (code "255") (name "unconnected-(U3-LHPOUT-Pad9)") (class "Default")
      (node (ref "U3") (pin "9") (pinfunction "LHPOUT_9") (pintype "bidirectional"))
    )
    (net (code "256") (name "unconnected-(U3-MICBIAS-Pad17)") (class "Default")
      (node (ref "U3") (pin "17") (pinfunction "MICBIAS_17") (pintype "bidirectional"))
    )
    (net (code "257") (name "unconnected-(U3-MICIN-Pad18)") (class "Default")
      (node (ref "U3") (pin "18") (pinfunction "MICIN_18") (pintype "bidirectional"))
    )
    (net (code "258") (name "unconnected-(U3-RHPOUT-Pad10)") (class "Default")
      (node (ref "U3") (pin "10") (pinfunction "RHPOUT_10") (pintype "bidirectional"))
    )
    (net (code "259") (name "unconnected-(U13B-CTRL-Pad6)") (class "Default")
      (node (ref "U13") (pin "6") (pinfunction "CTRL_6") (pintype "input"))
    )
    (net (code "260") (name "unconnected-(U13B-OUT-Pad5)") (class "Default")
      (node (ref "U13") (pin "5") (pinfunction "OUT_5") (pintype "output"))
    )
    (net (code "261") (name "unconnected-(U13D-CTRL-Pad14)") (class "Default")
      (node (ref "U13") (pin "14") (pinfunction "CTRL_14") (pintype "input"))
    )
    (net (code "262") (name "unconnected-(U13D-OUT-Pad13)") (class "Default")
      (node (ref "U13") (pin "13") (pinfunction "OUT_13") (pintype "output"))
    )
    (net (code "263") (name "unconnected-(U13E-MODE-Pad1)") (class "Default")
      (node (ref "U13") (pin "1") (pinfunction "MODE_1") (pintype "input"))
    )
    (net (code "264") (name "unconnected-(U18E-MODE-Pad1)") (class "Default")
      (node (ref "U18") (pin "1") (pinfunction "MODE_1") (pintype "input"))
    )
  )
)
